# M7105B.net
KiCad netlist of a schematic drawn in EAGLE
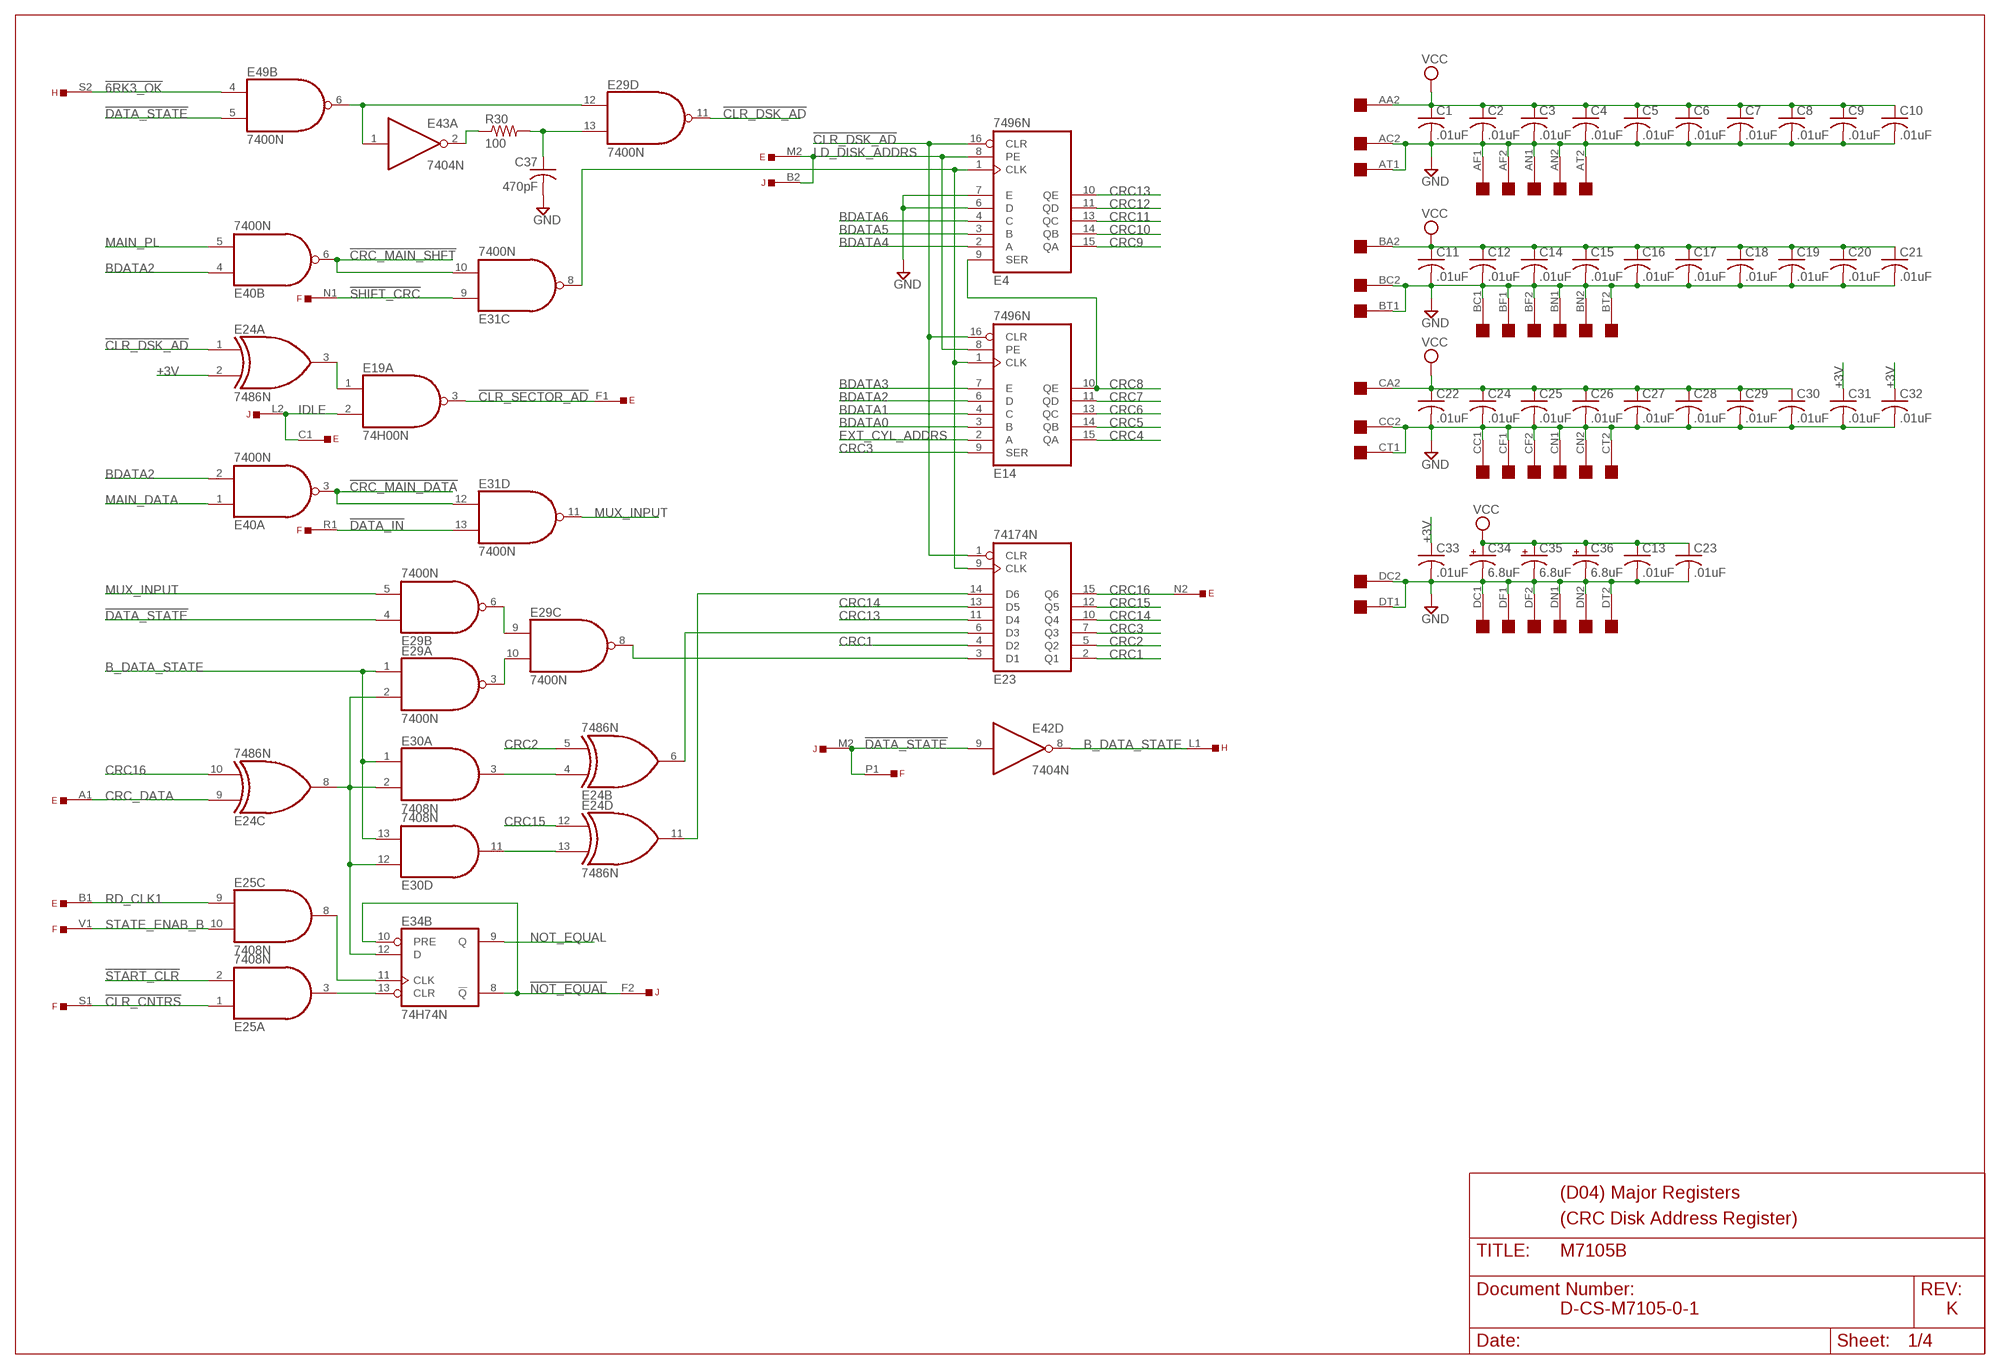
[diagram p0: schematic, sheet 1]
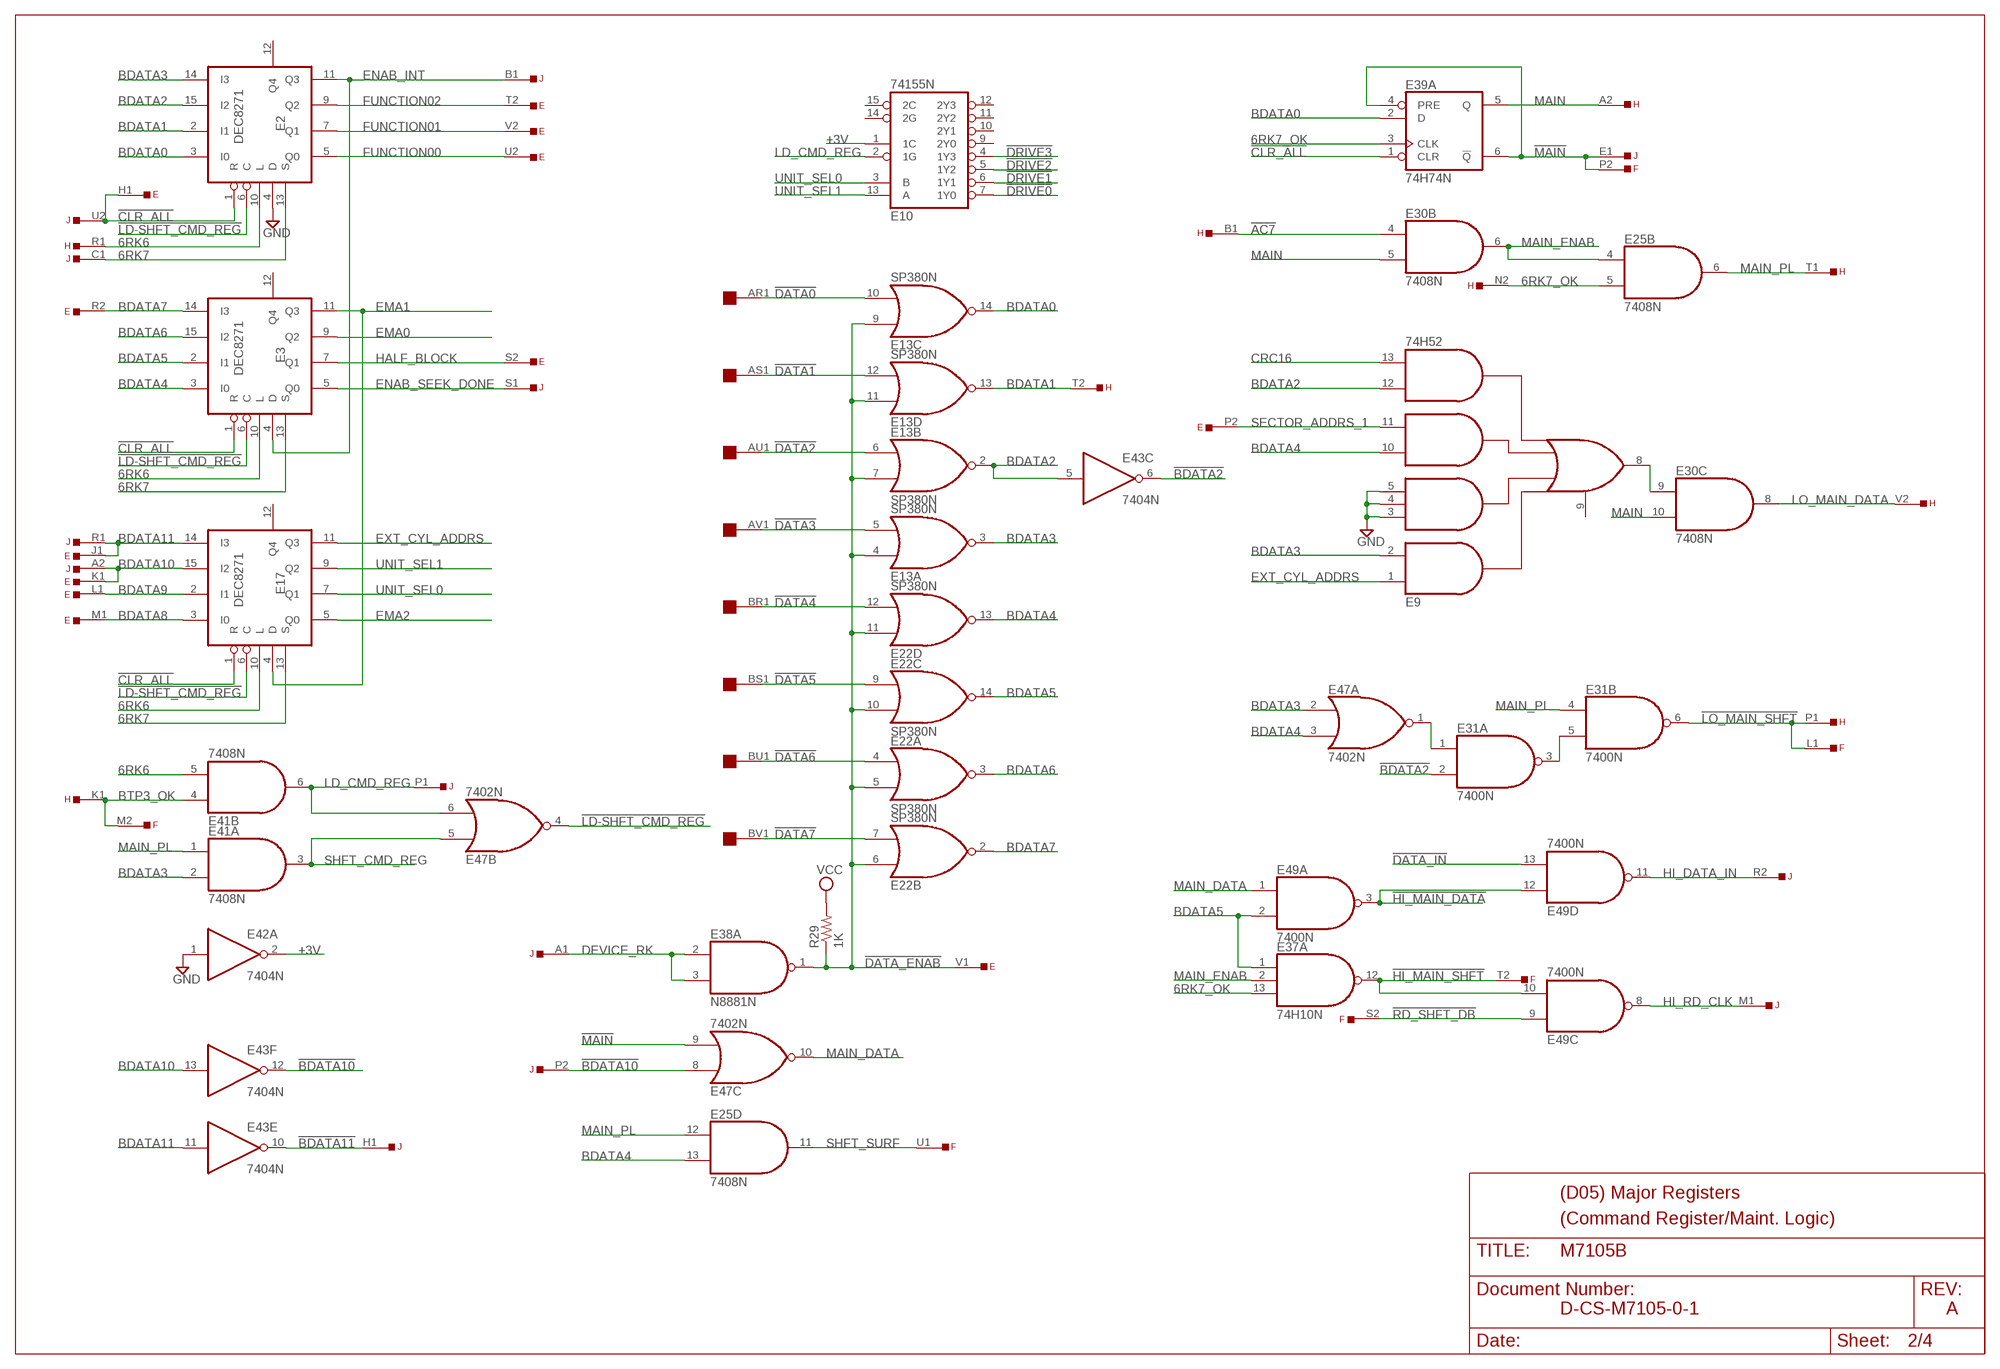
[diagram p1: schematic, sheet 2]
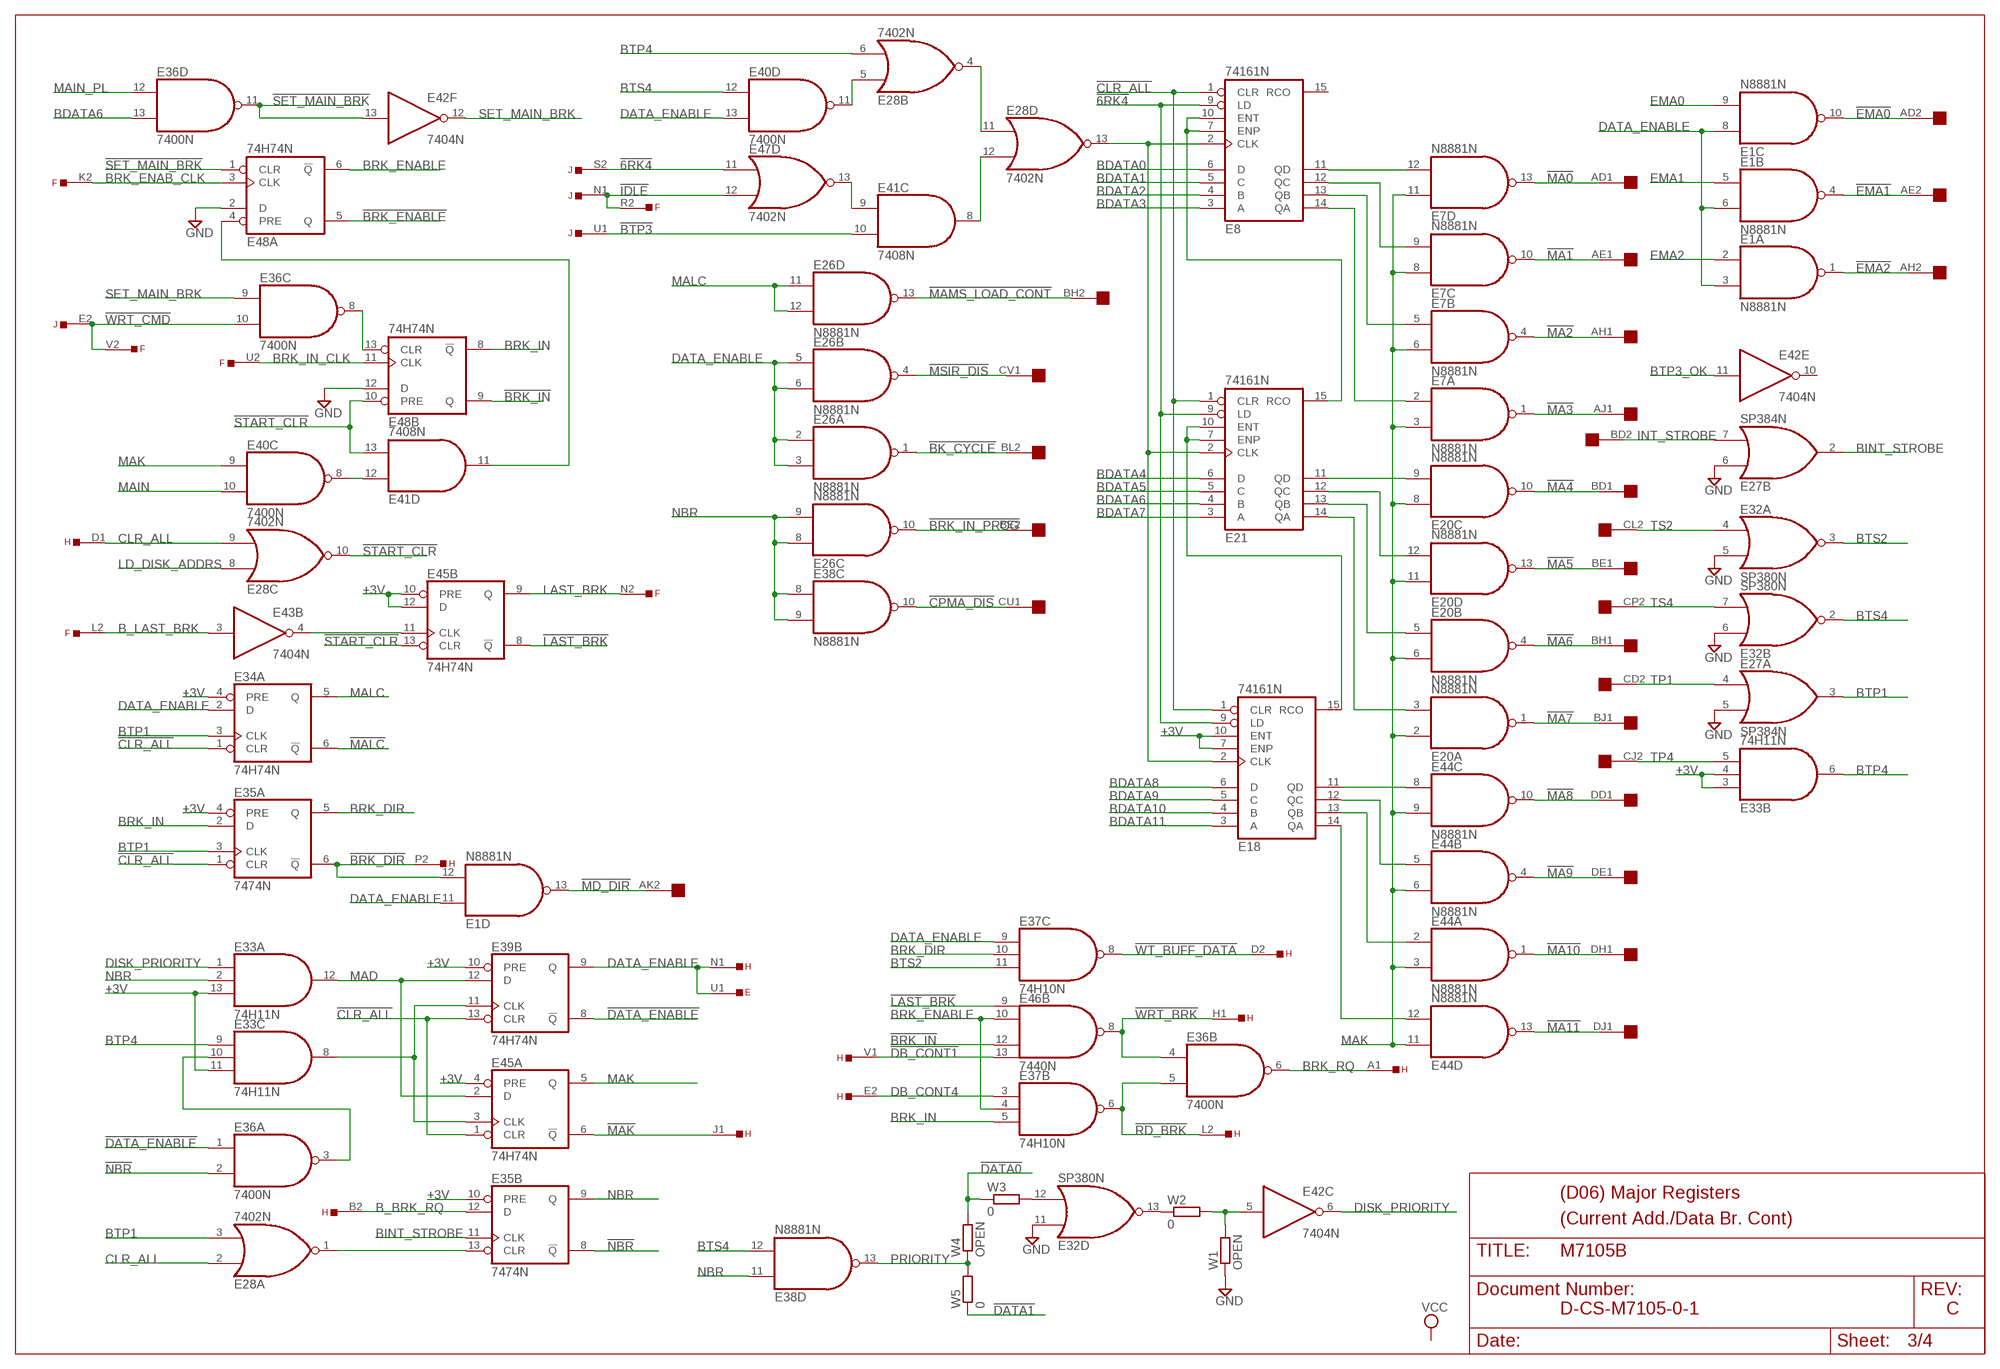
[diagram p2: schematic, sheet 3]
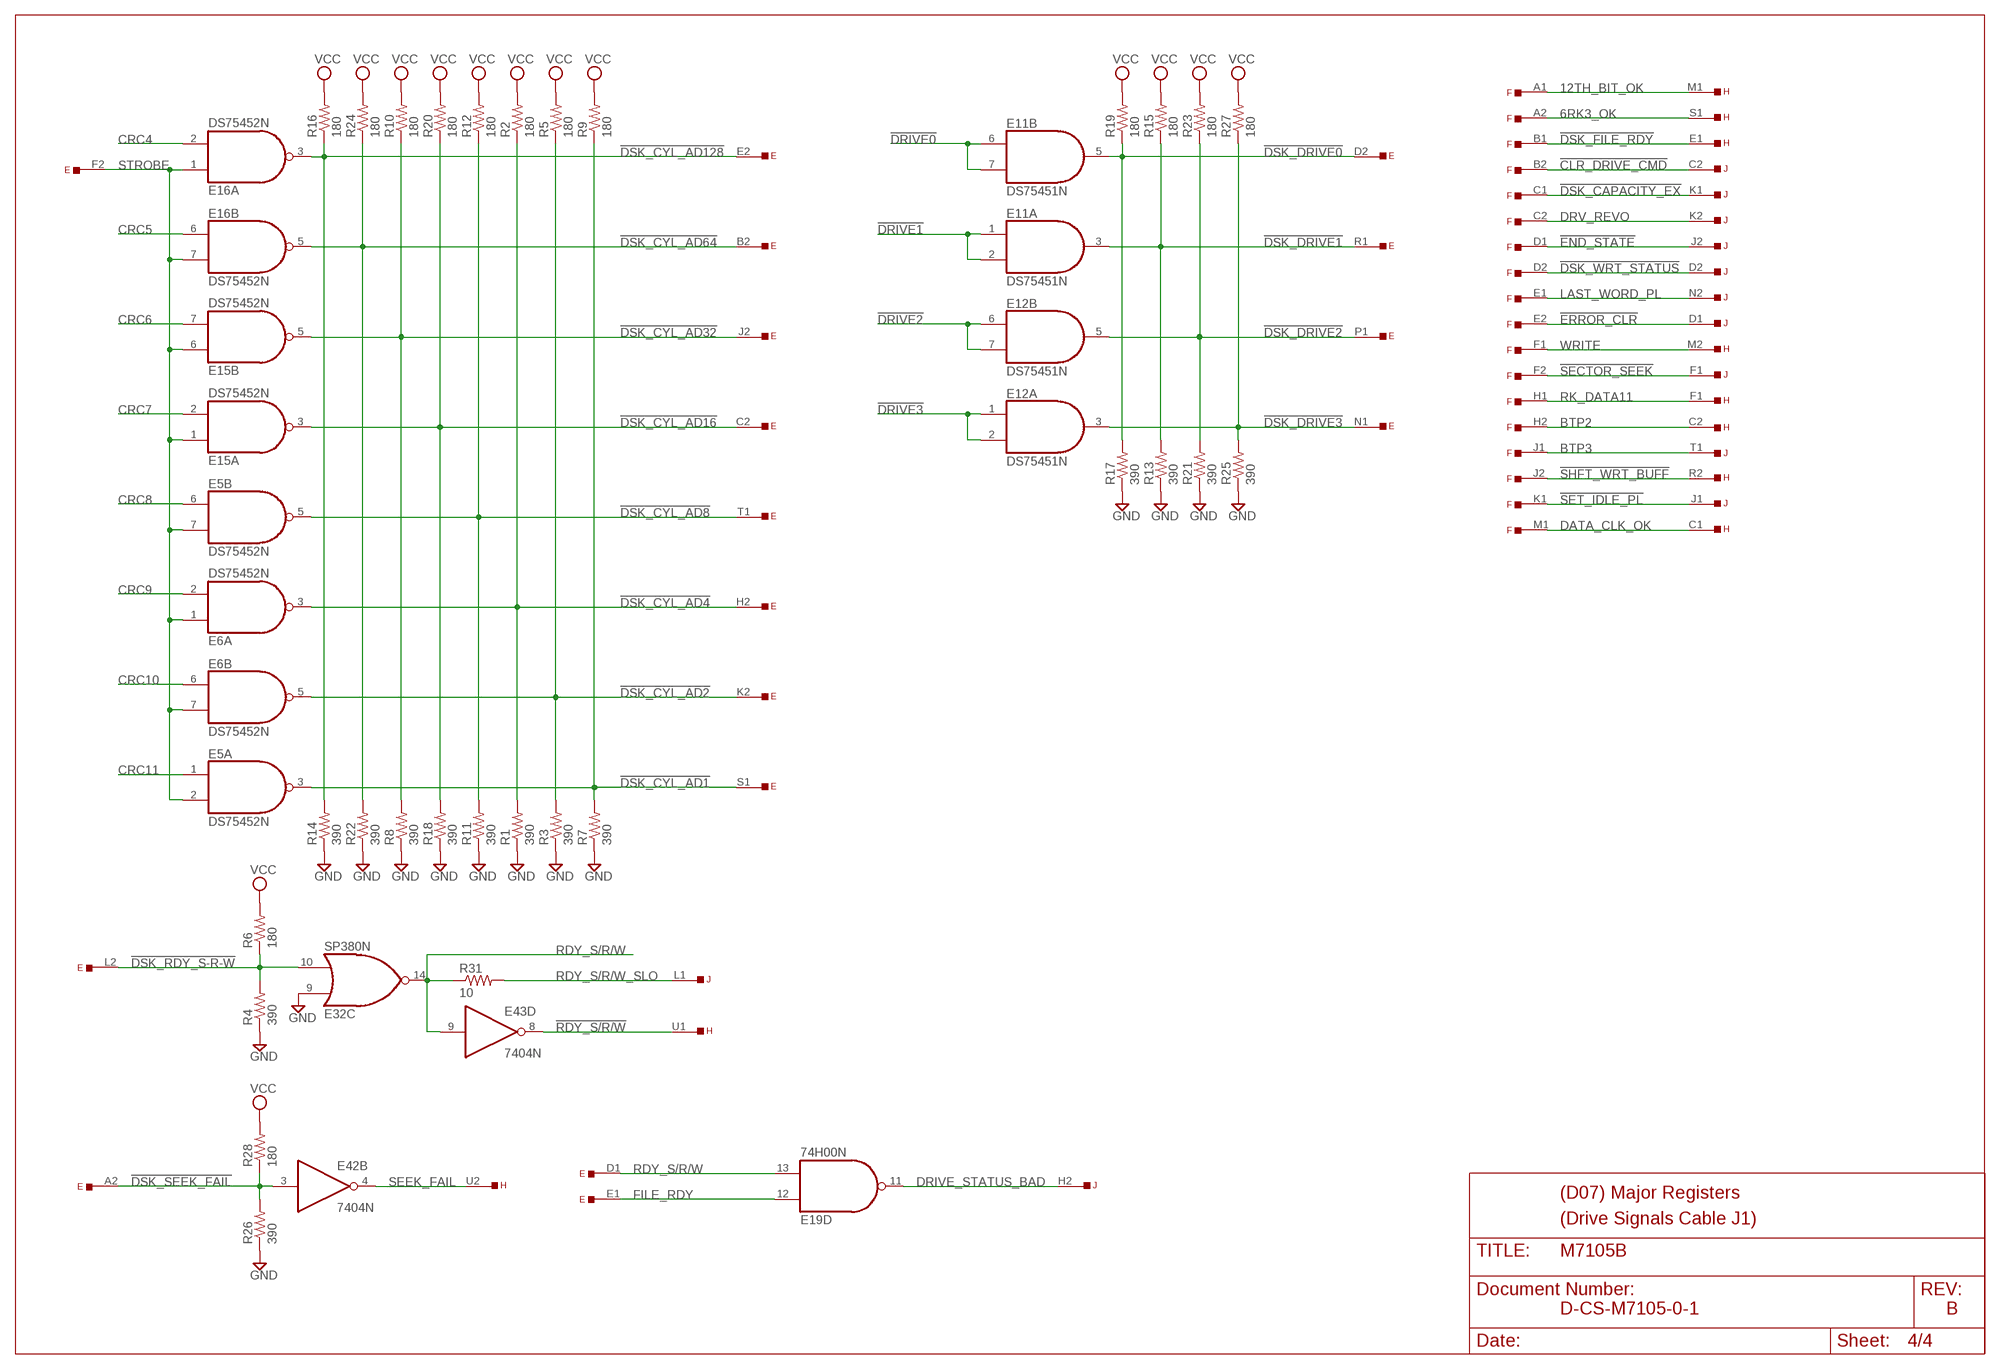
[diagram p3: schematic, sheet 4]

(export (version "E")
  (design (tool "Eeschema 10.0.6"))
  (components
    (comp (ref "E")
      (value "EDGE-TOP")
      (footprint "eagle-import:EDGE-CON2")
      (libsource (lib "eagle-import") (part "EDGE-TOP"))
    )
    (comp (ref "E2")
      (value "DEC8271")
      (footprint "eagle-import:DIL16")
      (libsource (lib "eagle-import") (part "DEC8271"))
    )
    (comp (ref "E3")
      (value "DEC8271")
      (footprint "eagle-import:DIL16")
      (libsource (lib "eagle-import") (part "DEC8271"))
    )
    (comp (ref "E9")
      (value "74H52")
      (footprint "eagle-import:DIL14")
      (libsource (lib "eagle-import") (part "7452H"))
    )
    (comp (ref "E10")
      (value "74155N")
      (footprint "eagle-import:DIL16")
      (libsource (lib "eagle-import") (part "74155N"))
    )
    (comp (ref "E13")
      (value "SP380N")
      (footprint "eagle-import:DIL14")
      (libsource (lib "eagle-import") (part "SP380N"))
    )
    (comp (ref "E17")
      (value "DEC8271")
      (footprint "eagle-import:DIL16")
      (libsource (lib "eagle-import") (part "DEC8271"))
    )
    (comp (ref "E22")
      (value "SP380N")
      (footprint "eagle-import:DIL14")
      (libsource (lib "eagle-import") (part "SP380N"))
    )
    (comp (ref "E25")
      (value "7408N")
      (footprint "eagle-import:DIL14")
      (libsource (lib "eagle-import") (part "7408NS"))
    )
    (comp (ref "E30")
      (value "7408N")
      (footprint "eagle-import:DIL14")
      (libsource (lib "eagle-import") (part "7408NS"))
    )
    (comp (ref "E31")
      (value "7400N")
      (footprint "eagle-import:DIL14")
      (libsource (lib "eagle-import") (part "7400N"))
    )
    (comp (ref "E37")
      (value "74H10N")
      (footprint "eagle-import:DIL14")
      (libsource (lib "eagle-import") (part "7410N"))
    )
    (comp (ref "E38")
      (value "N8881N")
      (footprint "eagle-import:DIL14")
      (libsource (lib "eagle-import") (part "N8881N"))
    )
    (comp (ref "E39")
      (value "74H74N")
      (footprint "eagle-import:DIL14")
      (libsource (lib "eagle-import") (part "7474NS"))
    )
    (comp (ref "E41")
      (value "7408N")
      (footprint "eagle-import:DIL14")
      (libsource (lib "eagle-import") (part "7408NS"))
    )
    (comp (ref "E42")
      (value "7404N")
      (footprint "eagle-import:DIL14")
      (libsource (lib "eagle-import") (part "7404N"))
    )
    (comp (ref "E43")
      (value "7404N")
      (footprint "eagle-import:DIL14")
      (libsource (lib "eagle-import") (part "7404N"))
    )
    (comp (ref "E47")
      (value "7402N")
      (footprint "eagle-import:DIL14")
      (libsource (lib "eagle-import") (part "7402N"))
    )
    (comp (ref "E49")
      (value "7400N")
      (footprint "eagle-import:DIL14")
      (libsource (lib "eagle-import") (part "7400N"))
    )
    (comp (ref "F")
      (value "EDGE-TOP")
      (footprint "eagle-import:EDGE-CON2")
      (libsource (lib "eagle-import") (part "EDGE-TOP"))
    )
    (comp (ref "H")
      (value "EDGE-TOP")
      (footprint "eagle-import:EDGE-CON2")
      (libsource (lib "eagle-import") (part "EDGE-TOP"))
    )
    (comp (ref "J")
      (value "EDGE-TOP")
      (footprint "eagle-import:EDGE-CON2")
      (libsource (lib "eagle-import") (part "EDGE-TOP"))
    )
    (comp (ref "OMNIBUS")
      (value "QUAD")
      (footprint "eagle-import:EDGE-CON8")
      (libsource (lib "eagle-import") (part "QUAD"))
    )
    (comp (ref "R29")
      (value "1K")
      (footprint "eagle-import:0207_10")
      (libsource (lib "eagle-import") (part "R-US_0207/10"))
    )
    (comp (ref "C1")
      (value ".01uF")
      (footprint "eagle-import:C063-025X075")
      (libsource (lib "eagle-import") (part "C-US"))
    )
    (comp (ref "C2")
      (value ".01uF")
      (footprint "eagle-import:C063-025X075")
      (libsource (lib "eagle-import") (part "C-US"))
    )
    (comp (ref "C3")
      (value ".01uF")
      (footprint "eagle-import:C063-025X075")
      (libsource (lib "eagle-import") (part "C-US"))
    )
    (comp (ref "C4")
      (value ".01uF")
      (footprint "eagle-import:C063-025X075")
      (libsource (lib "eagle-import") (part "C-US"))
    )
    (comp (ref "C5")
      (value ".01uF")
      (footprint "eagle-import:C063-025X075")
      (libsource (lib "eagle-import") (part "C-US"))
    )
    (comp (ref "C6")
      (value ".01uF")
      (footprint "eagle-import:C063-025X075")
      (libsource (lib "eagle-import") (part "C-US"))
    )
    (comp (ref "C7")
      (value ".01uF")
      (footprint "eagle-import:C063-025X075")
      (libsource (lib "eagle-import") (part "C-US"))
    )
    (comp (ref "C8")
      (value ".01uF")
      (footprint "eagle-import:C063-025X075")
      (libsource (lib "eagle-import") (part "C-US"))
    )
    (comp (ref "C9")
      (value ".01uF")
      (footprint "eagle-import:C063-025X075")
      (libsource (lib "eagle-import") (part "C-US"))
    )
    (comp (ref "C10")
      (value ".01uF")
      (footprint "eagle-import:C063-025X075")
      (libsource (lib "eagle-import") (part "C-US"))
    )
    (comp (ref "C11")
      (value ".01uF")
      (footprint "eagle-import:C063-025X075")
      (libsource (lib "eagle-import") (part "C-US"))
    )
    (comp (ref "C12")
      (value ".01uF")
      (footprint "eagle-import:C063-025X075")
      (libsource (lib "eagle-import") (part "C-US"))
    )
    (comp (ref "C13")
      (value ".01uF")
      (footprint "eagle-import:C063-025X075")
      (libsource (lib "eagle-import") (part "C-US"))
    )
    (comp (ref "C14")
      (value ".01uF")
      (footprint "eagle-import:C063-025X075")
      (libsource (lib "eagle-import") (part "C-US"))
    )
    (comp (ref "C15")
      (value ".01uF")
      (footprint "eagle-import:C063-025X075")
      (libsource (lib "eagle-import") (part "C-US"))
    )
    (comp (ref "C16")
      (value ".01uF")
      (footprint "eagle-import:C063-025X075")
      (libsource (lib "eagle-import") (part "C-US"))
    )
    (comp (ref "C17")
      (value ".01uF")
      (footprint "eagle-import:C063-025X075")
      (libsource (lib "eagle-import") (part "C-US"))
    )
    (comp (ref "C18")
      (value ".01uF")
      (footprint "eagle-import:C063-025X075")
      (libsource (lib "eagle-import") (part "C-US"))
    )
    (comp (ref "C19")
      (value ".01uF")
      (footprint "eagle-import:C063-025X075")
      (libsource (lib "eagle-import") (part "C-US"))
    )
    (comp (ref "C20")
      (value ".01uF")
      (footprint "eagle-import:C063-025X075")
      (libsource (lib "eagle-import") (part "C-US"))
    )
    (comp (ref "C21")
      (value ".01uF")
      (footprint "eagle-import:C063-025X075")
      (libsource (lib "eagle-import") (part "C-US"))
    )
    (comp (ref "C22")
      (value ".01uF")
      (footprint "eagle-import:C063-025X075")
      (libsource (lib "eagle-import") (part "C-US"))
    )
    (comp (ref "C23")
      (value ".01uF")
      (footprint "eagle-import:C063-025X075")
      (libsource (lib "eagle-import") (part "C-US"))
    )
    (comp (ref "C24")
      (value ".01uF")
      (footprint "eagle-import:C063-025X075")
      (libsource (lib "eagle-import") (part "C-US"))
    )
    (comp (ref "C25")
      (value ".01uF")
      (footprint "eagle-import:C063-025X075")
      (libsource (lib "eagle-import") (part "C-US"))
    )
    (comp (ref "C26")
      (value ".01uF")
      (footprint "eagle-import:C063-025X075")
      (libsource (lib "eagle-import") (part "C-US"))
    )
    (comp (ref "C27")
      (value ".01uF")
      (footprint "eagle-import:C063-025X075")
      (libsource (lib "eagle-import") (part "C-US"))
    )
    (comp (ref "C28")
      (value ".01uF")
      (footprint "eagle-import:C063-025X075")
      (libsource (lib "eagle-import") (part "C-US"))
    )
    (comp (ref "C29")
      (value ".01uF")
      (footprint "eagle-import:C063-025X075")
      (libsource (lib "eagle-import") (part "C-US"))
    )
    (comp (ref "C30")
      (value ".01uF")
      (footprint "eagle-import:C063-025X075")
      (libsource (lib "eagle-import") (part "C-US"))
    )
    (comp (ref "C31")
      (value ".01uF")
      (footprint "eagle-import:C063-025X075")
      (libsource (lib "eagle-import") (part "C-US"))
    )
    (comp (ref "C32")
      (value ".01uF")
      (footprint "eagle-import:C063-025X075")
      (libsource (lib "eagle-import") (part "C-US"))
    )
    (comp (ref "C33")
      (value ".01uF")
      (footprint "eagle-import:C063-025X075")
      (libsource (lib "eagle-import") (part "C-US"))
    )
    (comp (ref "C34")
      (value "6.8uF")
      (footprint "eagle-import:E12-8")
      (libsource (lib "eagle-import") (part "CPOL-USE20-8AXIAL"))
    )
    (comp (ref "C35")
      (value "6.8uF")
      (footprint "eagle-import:E12-8")
      (libsource (lib "eagle-import") (part "CPOL-USE20-8AXIAL"))
    )
    (comp (ref "C36")
      (value "6.8uF")
      (footprint "eagle-import:E12-8")
      (libsource (lib "eagle-import") (part "CPOL-USE20-8AXIAL"))
    )
    (comp (ref "C37")
      (value "470pF")
      (footprint "eagle-import:C063-025X075")
      (libsource (lib "eagle-import") (part "C-US"))
    )
    (comp (ref "E4")
      (value "7496N")
      (footprint "eagle-import:DIL16")
      (libsource (lib "eagle-import") (part "7496NLS"))
    )
    (comp (ref "E14")
      (value "7496N")
      (footprint "eagle-import:DIL16")
      (libsource (lib "eagle-import") (part "7496NLS"))
    )
    (comp (ref "E19")
      (value "74H00N")
      (footprint "eagle-import:DIL14")
      (libsource (lib "eagle-import") (part "7400NS"))
    )
    (comp (ref "E23")
      (value "74174N")
      (footprint "eagle-import:DIL16")
      (libsource (lib "eagle-import") (part "74174N"))
    )
    (comp (ref "E24")
      (value "7486N")
      (footprint "eagle-import:DIL14")
      (libsource (lib "eagle-import") (part "7486N"))
    )
    (comp (ref "E29")
      (value "7400N")
      (footprint "eagle-import:DIL14")
      (libsource (lib "eagle-import") (part "7400N"))
    )
    (comp (ref "E34")
      (value "74H74N")
      (footprint "eagle-import:DIL14")
      (libsource (lib "eagle-import") (part "7474NS"))
    )
    (comp (ref "E40")
      (value "7400N")
      (footprint "eagle-import:DIL14")
      (libsource (lib "eagle-import") (part "7400N"))
    )
    (comp (ref "R30")
      (value "100")
      (footprint "eagle-import:0207_10")
      (libsource (lib "eagle-import") (part "R-US_0207/10"))
    )
    (comp (ref "E1")
      (value "N8881N")
      (footprint "eagle-import:DIL14")
      (libsource (lib "eagle-import") (part "N8881N"))
    )
    (comp (ref "E7")
      (value "N8881N")
      (footprint "eagle-import:DIL14")
      (libsource (lib "eagle-import") (part "N8881N"))
    )
    (comp (ref "E8")
      (value "74161N")
      (footprint "eagle-import:DIL16")
      (libsource (lib "eagle-import") (part "74161N"))
    )
    (comp (ref "E18")
      (value "74161N")
      (footprint "eagle-import:DIL16")
      (libsource (lib "eagle-import") (part "74161N"))
    )
    (comp (ref "E20")
      (value "N8881N")
      (footprint "eagle-import:DIL14")
      (libsource (lib "eagle-import") (part "N8881N"))
    )
    (comp (ref "E21")
      (value "74161N")
      (footprint "eagle-import:DIL16")
      (libsource (lib "eagle-import") (part "74161N"))
    )
    (comp (ref "E26")
      (value "N8881N")
      (footprint "eagle-import:DIL14")
      (libsource (lib "eagle-import") (part "N8881N"))
    )
    (comp (ref "E27")
      (value "SP384N")
      (footprint "eagle-import:DIL14")
      (libsource (lib "eagle-import") (part "SP384N"))
    )
    (comp (ref "E28")
      (value "7402N")
      (footprint "eagle-import:DIL14")
      (libsource (lib "eagle-import") (part "7402N"))
    )
    (comp (ref "E32")
      (value "SP380N")
      (footprint "eagle-import:DIL14")
      (libsource (lib "eagle-import") (part "SP380N"))
    )
    (comp (ref "E33")
      (value "74H11N")
      (footprint "eagle-import:DIL14")
      (libsource (lib "eagle-import") (part "7411NS"))
    )
    (comp (ref "E35")
      (value "7474N")
      (footprint "eagle-import:DIL14")
      (libsource (lib "eagle-import") (part "7474NS"))
    )
    (comp (ref "E36")
      (value "7400N")
      (footprint "eagle-import:DIL14")
      (libsource (lib "eagle-import") (part "7400N"))
    )
    (comp (ref "E44")
      (value "N8881N")
      (footprint "eagle-import:DIL14")
      (libsource (lib "eagle-import") (part "N8881N"))
    )
    (comp (ref "E45")
      (value "74H74N")
      (footprint "eagle-import:DIL14")
      (libsource (lib "eagle-import") (part "7474NS"))
    )
    (comp (ref "E46")
      (value "7440N")
      (footprint "eagle-import:DIL14")
      (libsource (lib "eagle-import") (part "7440N"))
    )
    (comp (ref "E48")
      (value "74H74N")
      (footprint "eagle-import:DIL14")
      (libsource (lib "eagle-import") (part "7474NS"))
    )
    (comp (ref "W1")
      (value "OPEN")
      (footprint "eagle-import:0204_7")
      (libsource (lib "eagle-import") (part "R-EU_0204/7"))
    )
    (comp (ref "W2")
      (value "0")
      (footprint "eagle-import:0204_7")
      (libsource (lib "eagle-import") (part "R-EU_0204/7"))
    )
    (comp (ref "W3")
      (value "0")
      (footprint "eagle-import:0204_5")
      (libsource (lib "eagle-import") (part "R-EU_0204/5"))
    )
    (comp (ref "W4")
      (value "OPEN")
      (footprint "eagle-import:0204_5")
      (libsource (lib "eagle-import") (part "R-EU_0204/5"))
    )
    (comp (ref "W5")
      (value "0")
      (footprint "eagle-import:0204_5")
      (libsource (lib "eagle-import") (part "R-EU_0204/5"))
    )
    (comp (ref "E5")
      (value "DS75452N")
      (footprint "eagle-import:DIL08")
      (libsource (lib "eagle-import") (part "DS75452N"))
    )
    (comp (ref "E6")
      (value "DS75452N")
      (footprint "eagle-import:DIL08")
      (libsource (lib "eagle-import") (part "DS75452N"))
    )
    (comp (ref "E11")
      (value "DS75451N")
      (footprint "eagle-import:DIL08")
      (libsource (lib "eagle-import") (part "DS75451N"))
    )
    (comp (ref "E12")
      (value "DS75451N")
      (footprint "eagle-import:DIL08")
      (libsource (lib "eagle-import") (part "DS75451N"))
    )
    (comp (ref "E15")
      (value "DS75452N")
      (footprint "eagle-import:DIL08")
      (libsource (lib "eagle-import") (part "DS75452N"))
    )
    (comp (ref "E16")
      (value "DS75452N")
      (footprint "eagle-import:DIL08")
      (libsource (lib "eagle-import") (part "DS75452N"))
    )
    (comp (ref "R1")
      (value "390")
      (footprint "eagle-import:0207_10")
      (libsource (lib "eagle-import") (part "R-US_0207/10"))
    )
    (comp (ref "R2")
      (value "180")
      (footprint "eagle-import:0207_10")
      (libsource (lib "eagle-import") (part "R-US_0207/10"))
    )
    (comp (ref "R3")
      (value "390")
      (footprint "eagle-import:0207_10")
      (libsource (lib "eagle-import") (part "R-US_0207/10"))
    )
    (comp (ref "R4")
      (value "390")
      (footprint "eagle-import:0207_10")
      (libsource (lib "eagle-import") (part "R-US_0207/10"))
    )
    (comp (ref "R5")
      (value "180")
      (footprint "eagle-import:0207_10")
      (libsource (lib "eagle-import") (part "R-US_0207/10"))
    )
    (comp (ref "R6")
      (value "180")
      (footprint "eagle-import:0207_10")
      (libsource (lib "eagle-import") (part "R-US_0207/10"))
    )
    (comp (ref "R7")
      (value "390")
      (footprint "eagle-import:0207_10")
      (libsource (lib "eagle-import") (part "R-US_0207/10"))
    )
    (comp (ref "R8")
      (value "390")
      (footprint "eagle-import:0207_10")
      (libsource (lib "eagle-import") (part "R-US_0207/10"))
    )
    (comp (ref "R9")
      (value "180")
      (footprint "eagle-import:0207_10")
      (libsource (lib "eagle-import") (part "R-US_0207/10"))
    )
    (comp (ref "R10")
      (value "180")
      (footprint "eagle-import:0207_10")
      (libsource (lib "eagle-import") (part "R-US_0207/10"))
    )
    (comp (ref "R11")
      (value "390")
      (footprint "eagle-import:0207_10")
      (libsource (lib "eagle-import") (part "R-US_0207/10"))
    )
    (comp (ref "R12")
      (value "180")
      (footprint "eagle-import:0207_10")
      (libsource (lib "eagle-import") (part "R-US_0207/10"))
    )
    (comp (ref "R13")
      (value "390")
      (footprint "eagle-import:0207_10")
      (libsource (lib "eagle-import") (part "R-US_0207/10"))
    )
    (comp (ref "R14")
      (value "390")
      (footprint "eagle-import:0207_10")
      (libsource (lib "eagle-import") (part "R-US_0207/10"))
    )
    (comp (ref "R15")
      (value "180")
      (footprint "eagle-import:0207_10")
      (libsource (lib "eagle-import") (part "R-US_0207/10"))
    )
    (comp (ref "R16")
      (value "180")
      (footprint "eagle-import:0207_10")
      (libsource (lib "eagle-import") (part "R-US_0207/10"))
    )
    (comp (ref "R17")
      (value "390")
      (footprint "eagle-import:0207_10")
      (libsource (lib "eagle-import") (part "R-US_0207/10"))
    )
    (comp (ref "R18")
      (value "390")
      (footprint "eagle-import:0207_10")
      (libsource (lib "eagle-import") (part "R-US_0207/10"))
    )
    (comp (ref "R19")
      (value "180")
      (footprint "eagle-import:0207_10")
      (libsource (lib "eagle-import") (part "R-US_0207/10"))
    )
    (comp (ref "R20")
      (value "180")
      (footprint "eagle-import:0207_10")
      (libsource (lib "eagle-import") (part "R-US_0207/10"))
    )
    (comp (ref "R21")
      (value "390")
      (footprint "eagle-import:0207_10")
      (libsource (lib "eagle-import") (part "R-US_0207/10"))
    )
    (comp (ref "R22")
      (value "390")
      (footprint "eagle-import:0207_10")
      (libsource (lib "eagle-import") (part "R-US_0207/10"))
    )
    (comp (ref "R23")
      (value "180")
      (footprint "eagle-import:0207_10")
      (libsource (lib "eagle-import") (part "R-US_0207/10"))
    )
    (comp (ref "R24")
      (value "180")
      (footprint "eagle-import:0207_10")
      (libsource (lib "eagle-import") (part "R-US_0207/10"))
    )
    (comp (ref "R25")
      (value "390")
      (footprint "eagle-import:0207_10")
      (libsource (lib "eagle-import") (part "R-US_0207/10"))
    )
    (comp (ref "R26")
      (value "390")
      (footprint "eagle-import:0207_10")
      (libsource (lib "eagle-import") (part "R-US_0207/10"))
    )
    (comp (ref "R27")
      (value "180")
      (footprint "eagle-import:0207_10")
      (libsource (lib "eagle-import") (part "R-US_0207/10"))
    )
    (comp (ref "R28")
      (value "180")
      (footprint "eagle-import:0207_10")
      (libsource (lib "eagle-import") (part "R-US_0207/10"))
    )
    (comp (ref "R31")
      (value "10")
      (footprint "eagle-import:0207_10")
      (libsource (lib "eagle-import") (part "R-US_0207/10"))
    )
  )
  (nets
    (net (code "1") (name "+3V") (class "Default")
      (node (ref "C31") (pin "1") (pinfunction "1_1") (pintype "passive"))
      (node (ref "C32") (pin "1") (pinfunction "1_1") (pintype "passive"))
      (node (ref "C33") (pin "1") (pinfunction "1_1") (pintype "passive"))
      (node (ref "E10") (pin "1") (pinfunction "1C_1") (pintype "input"))
      (node (ref "E18") (pin "10") (pinfunction "ENT_10") (pintype "input"))
      (node (ref "E18") (pin "7") (pinfunction "ENP_7") (pintype "input"))
      (node (ref "E24") (pin "2") (pinfunction "I1_2") (pintype "input"))
      (node (ref "E33") (pin "11") (pinfunction "I2_11") (pintype "input"))
      (node (ref "E33") (pin "13") (pinfunction "I2_13") (pintype "input"))
      (node (ref "E33") (pin "3") (pinfunction "I0_3") (pintype "input"))
      (node (ref "E33") (pin "4") (pinfunction "I1_4") (pintype "input"))
      (node (ref "E34") (pin "4") (pinfunction "PRE_4") (pintype "input"))
      (node (ref "E35") (pin "10") (pinfunction "PRE_10") (pintype "input"))
      (node (ref "E35") (pin "4") (pinfunction "PRE_4") (pintype "input"))
      (node (ref "E39") (pin "10") (pinfunction "PRE_10") (pintype "input"))
      (node (ref "E42") (pin "2") (pinfunction "O_2") (pintype "output"))
      (node (ref "E45") (pin "10") (pinfunction "PRE_10") (pintype "input"))
      (node (ref "E45") (pin "12") (pinfunction "D_12") (pintype "input"))
      (node (ref "E45") (pin "4") (pinfunction "PRE_4") (pintype "input"))
    )
    (net (code "2") (name "6RK3_OK") (class "Default")
      (node (ref "F") (pin "A2") (pinfunction "P_A2") (pintype "passive"))
      (node (ref "H") (pin "S1") (pinfunction "P_S1") (pintype "passive"))
    )
    (net (code "3") (name "6RK6") (class "Default")
      (node (ref "E17") (pin "10") (pinfunction "L_10") (pintype "input"))
      (node (ref "E2") (pin "10") (pinfunction "L_10") (pintype "input"))
      (node (ref "E3") (pin "10") (pinfunction "L_10") (pintype "input"))
      (node (ref "E41") (pin "5") (pinfunction "I1_5") (pintype "input"))
      (node (ref "H") (pin "R1") (pinfunction "P_R1") (pintype "passive"))
    )
    (net (code "4") (name "6RK7") (class "Default")
      (node (ref "E17") (pin "13") (pinfunction "S_13") (pintype "input"))
      (node (ref "E2") (pin "13") (pinfunction "S_13") (pintype "input"))
      (node (ref "E3") (pin "13") (pinfunction "S_13") (pintype "input"))
      (node (ref "J") (pin "C1") (pinfunction "P_C1") (pintype "passive"))
    )
    (net (code "5") (name "6RK7_OK") (class "Default")
      (node (ref "E25") (pin "5") (pinfunction "I1_5") (pintype "input"))
      (node (ref "E37") (pin "13") (pinfunction "I2_13") (pintype "input"))
      (node (ref "E39") (pin "3") (pinfunction "CLK_3") (pintype "input"))
      (node (ref "H") (pin "N2") (pinfunction "P_N2") (pintype "passive"))
    )
    (net (code "6") (name "12TH_BIT_OK") (class "Default")
      (node (ref "F") (pin "A1") (pinfunction "P_A1") (pintype "passive"))
      (node (ref "H") (pin "M1") (pinfunction "P_M1") (pintype "passive"))
    )
    (net (code "7") (name "BDATA0") (class "Default")
      (node (ref "E13") (pin "14") (pinfunction "O_14") (pintype "output"))
      (node (ref "E14") (pin "3") (pinfunction "B_3") (pintype "input"))
      (node (ref "E2") (pin "3") (pinfunction "I0_3") (pintype "input"))
      (node (ref "E39") (pin "2") (pinfunction "D_2") (pintype "input"))
      (node (ref "E8") (pin "6") (pinfunction "D_6") (pintype "input"))
    )
    (net (code "8") (name "BDATA1") (class "Default")
      (node (ref "E13") (pin "13") (pinfunction "O_13") (pintype "output"))
      (node (ref "E14") (pin "4") (pinfunction "C_4") (pintype "input"))
      (node (ref "E2") (pin "2") (pinfunction "I1_2") (pintype "input"))
      (node (ref "E8") (pin "5") (pinfunction "C_5") (pintype "input"))
      (node (ref "H") (pin "T2") (pinfunction "P_T2") (pintype "passive"))
    )
    (net (code "9") (name "BDATA2") (class "Default")
      (node (ref "E13") (pin "2") (pinfunction "O_2") (pintype "output"))
      (node (ref "E14") (pin "6") (pinfunction "D_6") (pintype "input"))
      (node (ref "E2") (pin "15") (pinfunction "I2_15") (pintype "input"))
      (node (ref "E40") (pin "2") (pinfunction "I1_2") (pintype "input"))
      (node (ref "E40") (pin "4") (pinfunction "I0_4") (pintype "input"))
      (node (ref "E43") (pin "5") (pinfunction "I_5") (pintype "input"))
      (node (ref "E8") (pin "4") (pinfunction "B_4") (pintype "input"))
      (node (ref "E9") (pin "12") (pinfunction "I12_12") (pintype "input"))
    )
    (net (code "10") (name "BDATA3") (class "Default")
      (node (ref "E13") (pin "3") (pinfunction "O_3") (pintype "output"))
      (node (ref "E14") (pin "7") (pinfunction "E_7") (pintype "input"))
      (node (ref "E2") (pin "14") (pinfunction "I3_14") (pintype "input"))
      (node (ref "E41") (pin "2") (pinfunction "I1_2") (pintype "input"))
      (node (ref "E47") (pin "2") (pinfunction "I0_2") (pintype "input"))
      (node (ref "E8") (pin "3") (pinfunction "A_3") (pintype "input"))
      (node (ref "E9") (pin "2") (pinfunction "I2_2") (pintype "input"))
    )
    (net (code "11") (name "BDATA4") (class "Default")
      (node (ref "E21") (pin "6") (pinfunction "D_6") (pintype "input"))
      (node (ref "E22") (pin "13") (pinfunction "O_13") (pintype "output"))
      (node (ref "E25") (pin "13") (pinfunction "I1_13") (pintype "input"))
      (node (ref "E3") (pin "3") (pinfunction "I0_3") (pintype "input"))
      (node (ref "E4") (pin "2") (pinfunction "A_2") (pintype "input"))
      (node (ref "E47") (pin "3") (pinfunction "I1_3") (pintype "input"))
      (node (ref "E9") (pin "10") (pinfunction "I10_10") (pintype "input"))
    )
    (net (code "12") (name "BDATA5") (class "Default")
      (node (ref "E21") (pin "5") (pinfunction "C_5") (pintype "input"))
      (node (ref "E22") (pin "14") (pinfunction "O_14") (pintype "output"))
      (node (ref "E3") (pin "2") (pinfunction "I1_2") (pintype "input"))
      (node (ref "E37") (pin "1") (pinfunction "I0_1") (pintype "input"))
      (node (ref "E4") (pin "3") (pinfunction "B_3") (pintype "input"))
      (node (ref "E49") (pin "2") (pinfunction "I1_2") (pintype "input"))
    )
    (net (code "13") (name "BDATA6") (class "Default")
      (node (ref "E21") (pin "4") (pinfunction "B_4") (pintype "input"))
      (node (ref "E22") (pin "3") (pinfunction "O_3") (pintype "output"))
      (node (ref "E3") (pin "15") (pinfunction "I2_15") (pintype "input"))
      (node (ref "E36") (pin "13") (pinfunction "I1_13") (pintype "input"))
      (node (ref "E4") (pin "4") (pinfunction "C_4") (pintype "input"))
    )
    (net (code "14") (name "BDATA7") (class "Default")
      (node (ref "E") (pin "R2") (pinfunction "P_R2") (pintype "passive"))
      (node (ref "E21") (pin "3") (pinfunction "A_3") (pintype "input"))
      (node (ref "E22") (pin "2") (pinfunction "O_2") (pintype "output"))
      (node (ref "E3") (pin "14") (pinfunction "I3_14") (pintype "input"))
    )
    (net (code "15") (name "BDATA8") (class "Default")
      (node (ref "E") (pin "M1") (pinfunction "P_M1") (pintype "passive"))
      (node (ref "E17") (pin "3") (pinfunction "I0_3") (pintype "input"))
      (node (ref "E18") (pin "6") (pinfunction "D_6") (pintype "input"))
    )
    (net (code "16") (name "BDATA9") (class "Default")
      (node (ref "E") (pin "L1") (pinfunction "P_L1") (pintype "passive"))
      (node (ref "E17") (pin "2") (pinfunction "I1_2") (pintype "input"))
      (node (ref "E18") (pin "5") (pinfunction "C_5") (pintype "input"))
    )
    (net (code "17") (name "BDATA10") (class "Default")
      (node (ref "E") (pin "K1") (pinfunction "P_K1") (pintype "passive"))
      (node (ref "E17") (pin "15") (pinfunction "I2_15") (pintype "input"))
      (node (ref "E18") (pin "4") (pinfunction "B_4") (pintype "input"))
      (node (ref "E43") (pin "13") (pinfunction "I_13") (pintype "input"))
      (node (ref "J") (pin "A2") (pinfunction "P_A2") (pintype "passive"))
    )
    (net (code "18") (name "BDATA11") (class "Default")
      (node (ref "E") (pin "J1") (pinfunction "P_J1") (pintype "passive"))
      (node (ref "E17") (pin "14") (pinfunction "I3_14") (pintype "input"))
      (node (ref "E18") (pin "3") (pinfunction "A_3") (pintype "input"))
      (node (ref "E43") (pin "11") (pinfunction "I_11") (pintype "input"))
      (node (ref "J") (pin "R1") (pinfunction "P_R1") (pintype "passive"))
    )
    (net (code "19") (name "BINT_STROBE") (class "Default")
      (node (ref "E27") (pin "2") (pinfunction "O_2") (pintype "output"))
      (node (ref "E35") (pin "11") (pinfunction "CLK_11") (pintype "input"))
    )
    (net (code "20") (name "BRK_DIR") (class "Default")
      (node (ref "E35") (pin "5") (pinfunction "Q_5") (pintype "output"))
      (node (ref "E37") (pin "10") (pinfunction "I1_10") (pintype "input"))
    )
    (net (code "21") (name "BRK_ENABLE") (class "Default")
      (node (ref "E37") (pin "4") (pinfunction "I1_4") (pintype "input"))
      (node (ref "E46") (pin "10") (pinfunction "I1_10") (pintype "input"))
      (node (ref "E48") (pin "6") (pinfunction "~{Q}_6") (pintype "output"))
    )
    (net (code "22") (name "BRK_ENAB_CLK") (class "Default")
      (node (ref "E48") (pin "3") (pinfunction "CLK_3") (pintype "input"))
      (node (ref "F") (pin "K2") (pinfunction "P_K2") (pintype "passive"))
    )
    (net (code "23") (name "BRK_IN") (class "Default")
      (node (ref "E35") (pin "2") (pinfunction "D_2") (pintype "input"))
      (node (ref "E37") (pin "5") (pinfunction "I2_5") (pintype "input"))
      (node (ref "E48") (pin "8") (pinfunction "~{Q}_8") (pintype "output"))
    )
    (net (code "24") (name "BRK_IN_CLK") (class "Default")
      (node (ref "E48") (pin "11") (pinfunction "CLK_11") (pintype "input"))
      (node (ref "F") (pin "U2") (pinfunction "P_U2") (pintype "passive"))
    )
    (net (code "25") (name "BRK_RQ") (class "Default")
      (node (ref "E36") (pin "6") (pinfunction "O_6") (pintype "output"))
      (node (ref "H") (pin "A1") (pinfunction "P_A1") (pintype "passive"))
    )
    (net (code "26") (name "BTP1") (class "Default")
      (node (ref "E27") (pin "3") (pinfunction "O_3") (pintype "output"))
      (node (ref "E28") (pin "3") (pinfunction "I1_3") (pintype "input"))
      (node (ref "E34") (pin "3") (pinfunction "CLK_3") (pintype "input"))
      (node (ref "E35") (pin "3") (pinfunction "CLK_3") (pintype "input"))
    )
    (net (code "27") (name "BTP2") (class "Default")
      (node (ref "F") (pin "H2") (pinfunction "P_H2") (pintype "passive"))
      (node (ref "H") (pin "C2") (pinfunction "P_C2") (pintype "passive"))
    )
    (net (code "28") (name "BTP3") (class "Default")
      (node (ref "F") (pin "J1") (pinfunction "P_J1") (pintype "passive"))
      (node (ref "J") (pin "T1") (pinfunction "P_T1") (pintype "passive"))
    )
    (net (code "29") (name "BTP3_OK") (class "Default")
      (node (ref "E41") (pin "4") (pinfunction "I0_4") (pintype "input"))
      (node (ref "E42") (pin "11") (pinfunction "I_11") (pintype "input"))
      (node (ref "F") (pin "M2") (pinfunction "P_M2") (pintype "passive"))
      (node (ref "H") (pin "K1") (pinfunction "P_K1") (pintype "passive"))
    )
    (net (code "30") (name "BTP4") (class "Default")
      (node (ref "E28") (pin "6") (pinfunction "I1_6") (pintype "input"))
      (node (ref "E33") (pin "6") (pinfunction "O_6") (pintype "output"))
      (node (ref "E33") (pin "9") (pinfunction "I0_9") (pintype "input"))
    )
    (net (code "31") (name "BTS2") (class "Default")
      (node (ref "E32") (pin "3") (pinfunction "O_3") (pintype "output"))
      (node (ref "E37") (pin "11") (pinfunction "I2_11") (pintype "input"))
    )
    (net (code "32") (name "BTS4") (class "Default")
      (node (ref "E32") (pin "2") (pinfunction "O_2") (pintype "output"))
      (node (ref "E38") (pin "12") (pinfunction "I1_12") (pintype "input"))
      (node (ref "E40") (pin "12") (pinfunction "I0_12") (pintype "input"))
    )
    (net (code "33") (name "B_BRK_RQ") (class "Default")
      (node (ref "E35") (pin "12") (pinfunction "D_12") (pintype "input"))
      (node (ref "H") (pin "B2") (pinfunction "P_B2") (pintype "passive"))
    )
    (net (code "34") (name "B_DATA_STATE") (class "Default")
      (node (ref "E29") (pin "1") (pinfunction "I0_1") (pintype "input"))
      (node (ref "E30") (pin "1") (pinfunction "I0_1") (pintype "input"))
      (node (ref "E30") (pin "13") (pinfunction "I1_13") (pintype "input"))
      (node (ref "E42") (pin "8") (pinfunction "O_8") (pintype "output"))
      (node (ref "H") (pin "L1") (pinfunction "P_L1") (pintype "passive"))
    )
    (net (code "35") (name "B_LAST_BRK") (class "Default")
      (node (ref "E43") (pin "3") (pinfunction "I_3") (pintype "input"))
      (node (ref "F") (pin "L2") (pinfunction "P_L2") (pintype "passive"))
    )
    (net (code "36") (name "CLR_ALL") (class "Default")
      (node (ref "E28") (pin "2") (pinfunction "I0_2") (pintype "input"))
      (node (ref "E28") (pin "9") (pinfunction "I1_9") (pintype "input"))
      (node (ref "H") (pin "D1") (pinfunction "P_D1") (pintype "passive"))
    )
    (net (code "37") (name "CRC1") (class "Default")
      (node (ref "E23") (pin "2") (pinfunction "Q1_2") (pintype "output"))
      (node (ref "E23") (pin "4") (pinfunction "D2_4") (pintype "input"))
    )
    (net (code "38") (name "CRC2") (class "Default")
      (node (ref "E23") (pin "5") (pinfunction "Q2_5") (pintype "output"))
      (node (ref "E24") (pin "5") (pinfunction "I1_5") (pintype "input"))
    )
    (net (code "39") (name "CRC3") (class "Default")
      (node (ref "E14") (pin "9") (pinfunction "SER_9") (pintype "input"))
      (node (ref "E23") (pin "7") (pinfunction "Q3_7") (pintype "output"))
    )
    (net (code "40") (name "CRC4") (class "Default")
      (node (ref "E14") (pin "15") (pinfunction "QA_15") (pintype "output"))
      (node (ref "E16") (pin "2") (pinfunction "I1_2") (pintype "input"))
    )
    (net (code "41") (name "CRC5") (class "Default")
      (node (ref "E14") (pin "14") (pinfunction "QB_14") (pintype "output"))
      (node (ref "E16") (pin "6") (pinfunction "I0_6") (pintype "input"))
    )
    (net (code "42") (name "CRC6") (class "Default")
      (node (ref "E14") (pin "13") (pinfunction "QC_13") (pintype "output"))
      (node (ref "E15") (pin "7") (pinfunction "I1_7") (pintype "input"))
    )
    (net (code "43") (name "CRC7") (class "Default")
      (node (ref "E14") (pin "11") (pinfunction "QD_11") (pintype "output"))
      (node (ref "E15") (pin "2") (pinfunction "I1_2") (pintype "input"))
    )
    (net (code "44") (name "CRC8") (class "Default")
      (node (ref "E14") (pin "10") (pinfunction "QE_10") (pintype "output"))
      (node (ref "E4") (pin "9") (pinfunction "SER_9") (pintype "input"))
      (node (ref "E5") (pin "6") (pinfunction "I0_6") (pintype "input"))
    )
    (net (code "45") (name "CRC9") (class "Default")
      (node (ref "E4") (pin "15") (pinfunction "QA_15") (pintype "output"))
      (node (ref "E6") (pin "2") (pinfunction "I1_2") (pintype "input"))
    )
    (net (code "46") (name "CRC10") (class "Default")
      (node (ref "E4") (pin "14") (pinfunction "QB_14") (pintype "output"))
      (node (ref "E6") (pin "6") (pinfunction "I0_6") (pintype "input"))
    )
    (net (code "47") (name "CRC11") (class "Default")
      (node (ref "E4") (pin "13") (pinfunction "QC_13") (pintype "output"))
      (node (ref "E5") (pin "1") (pinfunction "I0_1") (pintype "input"))
    )
    (net (code "48") (name "CRC12") (class "Default")
      (node (ref "E4") (pin "11") (pinfunction "QD_11") (pintype "output"))
    )
    (net (code "49") (name "CRC13") (class "Default")
      (node (ref "E23") (pin "11") (pinfunction "D4_11") (pintype "input"))
      (node (ref "E4") (pin "10") (pinfunction "QE_10") (pintype "output"))
    )
    (net (code "50") (name "CRC14") (class "Default")
      (node (ref "E23") (pin "10") (pinfunction "Q4_10") (pintype "output"))
      (node (ref "E23") (pin "13") (pinfunction "D5_13") (pintype "input"))
    )
    (net (code "51") (name "CRC15") (class "Default")
      (node (ref "E23") (pin "12") (pinfunction "Q5_12") (pintype "output"))
      (node (ref "E24") (pin "12") (pinfunction "I0_12") (pintype "input"))
    )
    (net (code "52") (name "CRC16") (class "Default")
      (node (ref "E") (pin "N2") (pinfunction "P_N2") (pintype "passive"))
      (node (ref "E23") (pin "15") (pinfunction "Q6_15") (pintype "output"))
      (node (ref "E24") (pin "10") (pinfunction "I1_10") (pintype "input"))
      (node (ref "E9") (pin "13") (pinfunction "I13_13") (pintype "input"))
    )
    (net (code "53") (name "CRC_DATA") (class "Default")
      (node (ref "E") (pin "A1") (pinfunction "P_A1") (pintype "passive"))
      (node (ref "E24") (pin "9") (pinfunction "I0_9") (pintype "input"))
    )
    (net (code "54") (name "DATA_CLK_OK") (class "Default")
      (node (ref "F") (pin "M1") (pinfunction "P_M1") (pintype "passive"))
      (node (ref "H") (pin "C1") (pinfunction "P_C1") (pintype "passive"))
    )
    (net (code "55") (name "DATA_ENABLE") (class "Default")
      (node (ref "E") (pin "U1") (pinfunction "P_U1") (pintype "passive"))
      (node (ref "E1") (pin "11") (pinfunction "I0_11") (pintype "input"))
      (node (ref "E1") (pin "3") (pinfunction "I1_3") (pintype "input"))
      (node (ref "E1") (pin "6") (pinfunction "I1_6") (pintype "input"))
      (node (ref "E1") (pin "8") (pinfunction "I0_8") (pintype "input"))
      (node (ref "E26") (pin "2") (pinfunction "I0_2") (pintype "input"))
      (node (ref "E26") (pin "3") (pinfunction "I1_3") (pintype "input"))
      (node (ref "E26") (pin "5") (pinfunction "I0_5") (pintype "input"))
      (node (ref "E26") (pin "6") (pinfunction "I1_6") (pintype "input"))
      (node (ref "E34") (pin "2") (pinfunction "D_2") (pintype "input"))
      (node (ref "E37") (pin "9") (pinfunction "I0_9") (pintype "input"))
      (node (ref "E39") (pin "9") (pinfunction "Q_9") (pintype "output"))
      (node (ref "E40") (pin "13") (pinfunction "I1_13") (pintype "input"))
      (node (ref "H") (pin "N1") (pinfunction "P_N1") (pintype "passive"))
    )
    (net (code "56") (name "DB_CONT4") (class "Default")
      (node (ref "E37") (pin "3") (pinfunction "I0_3") (pintype "input"))
      (node (ref "H") (pin "E2") (pinfunction "P_E2") (pintype "passive"))
    )
    (net (code "57") (name "DEVICE_RK") (class "Default")
      (node (ref "E38") (pin "2") (pinfunction "I0_2") (pintype "input"))
      (node (ref "E38") (pin "3") (pinfunction "I1_3") (pintype "input"))
      (node (ref "J") (pin "A1") (pinfunction "P_A1") (pintype "passive"))
    )
    (net (code "58") (name "DISK_PRIORITY") (class "Default")
      (node (ref "E33") (pin "1") (pinfunction "I0_1") (pintype "input"))
      (node (ref "E42") (pin "6") (pinfunction "O_6") (pintype "output"))
    )
    (net (code "59") (name "DRIVE_STATUS_BAD") (class "Default")
      (node (ref "E19") (pin "11") (pinfunction "O_11") (pintype "output"))
      (node (ref "J") (pin "H2") (pinfunction "P_H2") (pintype "passive"))
    )
    (net (code "60") (name "DRV_REVO") (class "Default")
      (node (ref "F") (pin "C2") (pinfunction "P_C2") (pintype "passive"))
      (node (ref "J") (pin "K2") (pinfunction "P_K2") (pintype "passive"))
    )
    (net (code "61") (name "EMA0") (class "Default")
      (node (ref "E1") (pin "9") (pinfunction "I1_9") (pintype "input"))
      (node (ref "E3") (pin "9") (pinfunction "Q2_9") (pintype "output"))
    )
    (net (code "62") (name "EMA1") (class "Default")
      (node (ref "E1") (pin "5") (pinfunction "I0_5") (pintype "input"))
      (node (ref "E17") (pin "4") (pinfunction "D_4") (pintype "input"))
      (node (ref "E3") (pin "11") (pinfunction "Q3_11") (pintype "output"))
    )
    (net (code "63") (name "EMA2") (class "Default")
      (node (ref "E1") (pin "2") (pinfunction "I0_2") (pintype "input"))
      (node (ref "E17") (pin "5") (pinfunction "Q0_5") (pintype "output"))
    )
    (net (code "64") (name "ENAB_INT") (class "Default")
      (node (ref "E2") (pin "11") (pinfunction "Q3_11") (pintype "output"))
      (node (ref "E3") (pin "4") (pinfunction "D_4") (pintype "input"))
      (node (ref "J") (pin "B1") (pinfunction "P_B1") (pintype "passive"))
    )
    (net (code "65") (name "ENAB_SEEK_DONE") (class "Default")
      (node (ref "E3") (pin "5") (pinfunction "Q0_5") (pintype "output"))
      (node (ref "J") (pin "S1") (pinfunction "P_S1") (pintype "passive"))
    )
    (net (code "66") (name "EXT_CYL_ADDRS") (class "Default")
      (node (ref "E14") (pin "2") (pinfunction "A_2") (pintype "input"))
      (node (ref "E17") (pin "11") (pinfunction "Q3_11") (pintype "output"))
      (node (ref "E9") (pin "1") (pinfunction "I1_1") (pintype "input"))
    )
    (net (code "67") (name "FILE_RDY") (class "Default")
      (node (ref "E") (pin "E1") (pinfunction "P_E1") (pintype "passive"))
      (node (ref "E19") (pin "12") (pinfunction "I0_12") (pintype "input"))
    )
    (net (code "68") (name "FUNCTION00") (class "Default")
      (node (ref "E") (pin "U2") (pinfunction "P_U2") (pintype "passive"))
      (node (ref "E2") (pin "5") (pinfunction "Q0_5") (pintype "output"))
    )
    (net (code "69") (name "FUNCTION01") (class "Default")
      (node (ref "E") (pin "V2") (pinfunction "P_V2") (pintype "passive"))
      (node (ref "E2") (pin "7") (pinfunction "Q1_7") (pintype "output"))
    )
    (net (code "70") (name "FUNCTION02") (class "Default")
      (node (ref "E") (pin "T2") (pinfunction "P_T2") (pintype "passive"))
      (node (ref "E2") (pin "9") (pinfunction "Q2_9") (pintype "output"))
    )
    (net (code "71") (name "GND") (class "Default")
      (node (ref "C1") (pin "2") (pinfunction "2_2") (pintype "passive"))
      (node (ref "C10") (pin "2") (pinfunction "2_2") (pintype "passive"))
      (node (ref "C11") (pin "2") (pinfunction "2_2") (pintype "passive"))
      (node (ref "C12") (pin "2") (pinfunction "2_2") (pintype "passive"))
      (node (ref "C13") (pin "2") (pinfunction "2_2") (pintype "passive"))
      (node (ref "C14") (pin "2") (pinfunction "2_2") (pintype "passive"))
      (node (ref "C15") (pin "2") (pinfunction "2_2") (pintype "passive"))
      (node (ref "C16") (pin "2") (pinfunction "2_2") (pintype "passive"))
      (node (ref "C17") (pin "2") (pinfunction "2_2") (pintype "passive"))
      (node (ref "C18") (pin "2") (pinfunction "2_2") (pintype "passive"))
      (node (ref "C19") (pin "2") (pinfunction "2_2") (pintype "passive"))
      (node (ref "C2") (pin "2") (pinfunction "2_2") (pintype "passive"))
      (node (ref "C20") (pin "2") (pinfunction "2_2") (pintype "passive"))
      (node (ref "C21") (pin "2") (pinfunction "2_2") (pintype "passive"))
      (node (ref "C22") (pin "2") (pinfunction "2_2") (pintype "passive"))
      (node (ref "C23") (pin "2") (pinfunction "2_2") (pintype "passive"))
      (node (ref "C24") (pin "2") (pinfunction "2_2") (pintype "passive"))
      (node (ref "C25") (pin "2") (pinfunction "2_2") (pintype "passive"))
      (node (ref "C26") (pin "2") (pinfunction "2_2") (pintype "passive"))
      (node (ref "C27") (pin "2") (pinfunction "2_2") (pintype "passive"))
      (node (ref "C28") (pin "2") (pinfunction "2_2") (pintype "passive"))
      (node (ref "C29") (pin "2") (pinfunction "2_2") (pintype "passive"))
      (node (ref "C3") (pin "2") (pinfunction "2_2") (pintype "passive"))
      (node (ref "C30") (pin "2") (pinfunction "2_2") (pintype "passive"))
      (node (ref "C31") (pin "2") (pinfunction "2_2") (pintype "passive"))
      (node (ref "C32") (pin "2") (pinfunction "2_2") (pintype "passive"))
      (node (ref "C33") (pin "2") (pinfunction "2_2") (pintype "passive"))
      (node (ref "C34") (pin "-") (pinfunction "-_-") (pintype "passive"))
      (node (ref "C35") (pin "-") (pinfunction "-_-") (pintype "passive"))
      (node (ref "C36") (pin "-") (pinfunction "-_-") (pintype "passive"))
      (node (ref "C37") (pin "2") (pinfunction "2_2") (pintype "passive"))
      (node (ref "C4") (pin "2") (pinfunction "2_2") (pintype "passive"))
      (node (ref "C5") (pin "2") (pinfunction "2_2") (pintype "passive"))
      (node (ref "C6") (pin "2") (pinfunction "2_2") (pintype "passive"))
      (node (ref "C7") (pin "2") (pinfunction "2_2") (pintype "passive"))
      (node (ref "C8") (pin "2") (pinfunction "2_2") (pintype "passive"))
      (node (ref "C9") (pin "2") (pinfunction "2_2") (pintype "passive"))
      (node (ref "E2") (pin "4") (pinfunction "D_4") (pintype "input"))
      (node (ref "E27") (pin "5") (pinfunction "I1_5") (pintype "input"))
      (node (ref "E27") (pin "6") (pinfunction "I0_6") (pintype "input"))
      (node (ref "E32") (pin "11") (pinfunction "I0_11") (pintype "input"))
      (node (ref "E32") (pin "5") (pinfunction "I1_5") (pintype "input"))
      (node (ref "E32") (pin "6") (pinfunction "I0_6") (pintype "input"))
      (node (ref "E32") (pin "9") (pinfunction "I0_9") (pintype "input"))
      (node (ref "E4") (pin "6") (pinfunction "D_6") (pintype "input"))
      (node (ref "E4") (pin "7") (pinfunction "E_7") (pintype "input"))
      (node (ref "E42") (pin "1") (pinfunction "I_1") (pintype "input"))
      (node (ref "E48") (pin "12") (pinfunction "D_12") (pintype "input"))
      (node (ref "E48") (pin "2") (pinfunction "D_2") (pintype "input"))
      (node (ref "E9") (pin "3") (pinfunction "I3_3") (pintype "input"))
      (node (ref "E9") (pin "4") (pinfunction "I4_4") (pintype "input"))
      (node (ref "E9") (pin "5") (pinfunction "I5_5") (pintype "input"))
      (node (ref "OMNIBUS") (pin "AC2") (pinfunction "1_AC2") (pintype "bidirectional"))
      (node (ref "OMNIBUS") (pin "AF1") (pinfunction "1_AF1") (pintype "bidirectional"))
      (node (ref "OMNIBUS") (pin "AF2") (pinfunction "1_AF2") (pintype "bidirectional"))
      (node (ref "OMNIBUS") (pin "AN1") (pinfunction "1_AN1") (pintype "bidirectional"))
      (node (ref "OMNIBUS") (pin "AN2") (pinfunction "1_AN2") (pintype "bidirectional"))
      (node (ref "OMNIBUS") (pin "AT1") (pinfunction "1_AT1") (pintype "bidirectional"))
      (node (ref "OMNIBUS") (pin "AT2") (pinfunction "1_AT2") (pintype "bidirectional"))
      (node (ref "OMNIBUS") (pin "BC1") (pinfunction "1_BC1") (pintype "bidirectional"))
      (node (ref "OMNIBUS") (pin "BC2") (pinfunction "1_BC2") (pintype "bidirectional"))
      (node (ref "OMNIBUS") (pin "BF1") (pinfunction "1_BF1") (pintype "bidirectional"))
      (node (ref "OMNIBUS") (pin "BF2") (pinfunction "1_BF2") (pintype "bidirectional"))
      (node (ref "OMNIBUS") (pin "BN1") (pinfunction "1_BN1") (pintype "bidirectional"))
      (node (ref "OMNIBUS") (pin "BN2") (pinfunction "1_BN2") (pintype "bidirectional"))
      (node (ref "OMNIBUS") (pin "BT1") (pinfunction "1_BT1") (pintype "bidirectional"))
      (node (ref "OMNIBUS") (pin "BT2") (pinfunction "1_BT2") (pintype "bidirectional"))
      (node (ref "OMNIBUS") (pin "CC1") (pinfunction "1_CC1") (pintype "bidirectional"))
      (node (ref "OMNIBUS") (pin "CC2") (pinfunction "1_CC2") (pintype "bidirectional"))
      (node (ref "OMNIBUS") (pin "CF1") (pinfunction "1_CF1") (pintype "bidirectional"))
      (node (ref "OMNIBUS") (pin "CF2") (pinfunction "1_CF2") (pintype "bidirectional"))
      (node (ref "OMNIBUS") (pin "CN1") (pinfunction "1_CN1") (pintype "bidirectional"))
      (node (ref "OMNIBUS") (pin "CN2") (pinfunction "1_CN2") (pintype "bidirectional"))
      (node (ref "OMNIBUS") (pin "CT1") (pinfunction "1_CT1") (pintype "bidirectional"))
      (node (ref "OMNIBUS") (pin "CT2") (pinfunction "1_CT2") (pintype "bidirectional"))
      (node (ref "OMNIBUS") (pin "DC1") (pinfunction "1_DC1") (pintype "bidirectional"))
      (node (ref "OMNIBUS") (pin "DC2") (pinfunction "1_DC2") (pintype "bidirectional"))
      (node (ref "OMNIBUS") (pin "DF1") (pinfunction "1_DF1") (pintype "bidirectional"))
      (node (ref "OMNIBUS") (pin "DF2") (pinfunction "1_DF2") (pintype "bidirectional"))
      (node (ref "OMNIBUS") (pin "DN1") (pinfunction "1_DN1") (pintype "bidirectional"))
      (node (ref "OMNIBUS") (pin "DN2") (pinfunction "1_DN2") (pintype "bidirectional"))
      (node (ref "OMNIBUS") (pin "DT1") (pinfunction "1_DT1") (pintype "bidirectional"))
      (node (ref "OMNIBUS") (pin "DT2") (pinfunction "1_DT2") (pintype "bidirectional"))
      (node (ref "R1") (pin "1") (pinfunction "1_1") (pintype "passive"))
      (node (ref "R11") (pin "1") (pinfunction "1_1") (pintype "passive"))
      (node (ref "R13") (pin "1") (pinfunction "1_1") (pintype "passive"))
      (node (ref "R14") (pin "1") (pinfunction "1_1") (pintype "passive"))
      (node (ref "R17") (pin "1") (pinfunction "1_1") (pintype "passive"))
      (node (ref "R18") (pin "1") (pinfunction "1_1") (pintype "passive"))
      (node (ref "R21") (pin "1") (pinfunction "1_1") (pintype "passive"))
      (node (ref "R22") (pin "1") (pinfunction "1_1") (pintype "passive"))
      (node (ref "R25") (pin "1") (pinfunction "1_1") (pintype "passive"))
      (node (ref "R26") (pin "1") (pinfunction "1_1") (pintype "passive"))
      (node (ref "R3") (pin "1") (pinfunction "1_1") (pintype "passive"))
      (node (ref "R4") (pin "1") (pinfunction "1_1") (pintype "passive"))
      (node (ref "R7") (pin "1") (pinfunction "1_1") (pintype "passive"))
      (node (ref "R8") (pin "1") (pinfunction "1_1") (pintype "passive"))
      (node (ref "W1") (pin "1") (pinfunction "1_1") (pintype "passive"))
    )
    (net (code "72") (name "HALF_BLOCK") (class "Default")
      (node (ref "E") (pin "S2") (pinfunction "P_S2") (pintype "passive"))
      (node (ref "E3") (pin "7") (pinfunction "Q1_7") (pintype "output"))
    )
    (net (code "73") (name "HI_DATA_IN") (class "Default")
      (node (ref "E49") (pin "11") (pinfunction "O_11") (pintype "output"))
      (node (ref "J") (pin "R2") (pinfunction "P_R2") (pintype "passive"))
    )
    (net (code "74") (name "HI_RD_CLK") (class "Default")
      (node (ref "E49") (pin "8") (pinfunction "O_8") (pintype "output"))
      (node (ref "J") (pin "M1") (pinfunction "P_M1") (pintype "passive"))
    )
    (net (code "75") (name "IDLE") (class "Default")
      (node (ref "E") (pin "C1") (pinfunction "P_C1") (pintype "passive"))
      (node (ref "E19") (pin "2") (pinfunction "I1_2") (pintype "input"))
      (node (ref "J") (pin "L2") (pinfunction "P_L2") (pintype "passive"))
    )
    (net (code "76") (name "INT_STROBE") (class "Default")
      (node (ref "E27") (pin "7") (pinfunction "I1_7") (pintype "input"))
      (node (ref "OMNIBUS") (pin "BD2") (pinfunction "1_BD2") (pintype "bidirectional"))
    )
    (net (code "77") (name "LAST_BRK") (class "Default")
      (node (ref "E45") (pin "9") (pinfunction "Q_9") (pintype "output"))
      (node (ref "F") (pin "N2") (pinfunction "P_N2") (pintype "passive"))
    )
    (net (code "78") (name "LAST_WORD_PL") (class "Default")
      (node (ref "F") (pin "E1") (pinfunction "P_E1") (pintype "passive"))
      (node (ref "J") (pin "N2") (pinfunction "P_N2") (pintype "passive"))
    )
    (net (code "79") (name "LD_CMD_REG") (class "Default")
      (node (ref "E10") (pin "2") (pinfunction "1G_2") (pintype "input"))
      (node (ref "E41") (pin "6") (pinfunction "O_6") (pintype "output"))
      (node (ref "E47") (pin "6") (pinfunction "I1_6") (pintype "input"))
      (node (ref "J") (pin "P1") (pinfunction "P_P1") (pintype "passive"))
    )
    (net (code "80") (name "LD_DISK_ADDRS") (class "Default")
      (node (ref "E") (pin "M2") (pinfunction "P_M2") (pintype "passive"))
      (node (ref "E14") (pin "8") (pinfunction "PE_8") (pintype "input"))
      (node (ref "E28") (pin "8") (pinfunction "I0_8") (pintype "input"))
      (node (ref "E4") (pin "8") (pinfunction "PE_8") (pintype "input"))
      (node (ref "J") (pin "B2") (pinfunction "P_B2") (pintype "passive"))
    )
    (net (code "81") (name "LO_MAIN_DATA") (class "Default")
      (node (ref "E30") (pin "8") (pinfunction "O_8") (pintype "output"))
      (node (ref "H") (pin "V2") (pinfunction "P_V2") (pintype "passive"))
    )
    (net (code "82") (name "MAD") (class "Default")
      (node (ref "E33") (pin "12") (pinfunction "O_12") (pintype "output"))
      (node (ref "E39") (pin "12") (pinfunction "D_12") (pintype "input"))
      (node (ref "E45") (pin "2") (pinfunction "D_2") (pintype "input"))
    )
    (net (code "83") (name "MAIN") (class "Default")
      (node (ref "E30") (pin "10") (pinfunction "I1_10") (pintype "input"))
      (node (ref "E30") (pin "5") (pinfunction "I1_5") (pintype "input"))
      (node (ref "E39") (pin "5") (pinfunction "Q_5") (pintype "output"))
      (node (ref "E40") (pin "10") (pinfunction "I1_10") (pintype "input"))
      (node (ref "H") (pin "A2") (pinfunction "P_A2") (pintype "passive"))
    )
    (net (code "84") (name "MAIN_DATA") (class "Default")
      (node (ref "E40") (pin "1") (pinfunction "I0_1") (pintype "input"))
      (node (ref "E47") (pin "10") (pinfunction "O_10") (pintype "output"))
      (node (ref "E49") (pin "1") (pinfunction "I0_1") (pintype "input"))
    )
    (net (code "85") (name "MAIN_ENAB") (class "Default")
      (node (ref "E25") (pin "4") (pinfunction "I0_4") (pintype "input"))
      (node (ref "E30") (pin "6") (pinfunction "O_6") (pintype "output"))
      (node (ref "E37") (pin "2") (pinfunction "I1_2") (pintype "input"))
    )
    (net (code "86") (name "MAIN_PL") (class "Default")
      (node (ref "E25") (pin "12") (pinfunction "I0_12") (pintype "input"))
      (node (ref "E25") (pin "6") (pinfunction "O_6") (pintype "output"))
      (node (ref "E31") (pin "4") (pinfunction "I0_4") (pintype "input"))
      (node (ref "E36") (pin "12") (pinfunction "I0_12") (pintype "input"))
      (node (ref "E40") (pin "5") (pinfunction "I1_5") (pintype "input"))
      (node (ref "E41") (pin "1") (pinfunction "I0_1") (pintype "input"))
      (node (ref "H") (pin "T1") (pinfunction "P_T1") (pintype "passive"))
    )
    (net (code "87") (name "MAK") (class "Default")
      (node (ref "E20") (pin "11") (pinfunction "I0_11") (pintype "input"))
      (node (ref "E20") (pin "2") (pinfunction "I0_2") (pintype "input"))
      (node (ref "E20") (pin "6") (pinfunction "I1_6") (pintype "input"))
      (node (ref "E20") (pin "8") (pinfunction "I0_8") (pintype "input"))
      (node (ref "E40") (pin "9") (pinfunction "I0_9") (pintype "input"))
      (node (ref "E44") (pin "11") (pinfunction "I0_11") (pintype "input"))
      (node (ref "E44") (pin "3") (pinfunction "I1_3") (pintype "input"))
      (node (ref "E44") (pin "6") (pinfunction "I1_6") (pintype "input"))
      (node (ref "E44") (pin "9") (pinfunction "I1_9") (pintype "input"))
      (node (ref "E45") (pin "5") (pinfunction "Q_5") (pintype "output"))
      (node (ref "E7") (pin "11") (pinfunction "I0_11") (pintype "input"))
      (node (ref "E7") (pin "3") (pinfunction "I1_3") (pintype "input"))
      (node (ref "E7") (pin "6") (pinfunction "I1_6") (pintype "input"))
      (node (ref "E7") (pin "8") (pinfunction "I0_8") (pintype "input"))
    )
    (net (code "88") (name "MALC") (class "Default")
      (node (ref "E26") (pin "11") (pinfunction "I0_11") (pintype "input"))
      (node (ref "E26") (pin "12") (pinfunction "I1_12") (pintype "input"))
      (node (ref "E34") (pin "5") (pinfunction "Q_5") (pintype "output"))
    )
    (net (code "89") (name "MUX_INPUT") (class "Default")
      (node (ref "E29") (pin "5") (pinfunction "I1_5") (pintype "input"))
      (node (ref "E31") (pin "11") (pinfunction "O_11") (pintype "output"))
    )
    (net (code "90") (name "NBR") (class "Default")
      (node (ref "E26") (pin "8") (pinfunction "I0_8") (pintype "input"))
      (node (ref "E26") (pin "9") (pinfunction "I1_9") (pintype "input"))
      (node (ref "E33") (pin "2") (pinfunction "I1_2") (pintype "input"))
      (node (ref "E35") (pin "9") (pinfunction "Q_9") (pintype "output"))
      (node (ref "E38") (pin "11") (pinfunction "I0_11") (pintype "input"))
      (node (ref "E38") (pin "8") (pinfunction "I0_8") (pintype "input"))
      (node (ref "E38") (pin "9") (pinfunction "I1_9") (pintype "input"))
    )
    (net (code "91") (name "NOT_EQUAL") (class "Default")
      (node (ref "E34") (pin "9") (pinfunction "Q_9") (pintype "output"))
    )
    (net (code "92") (name "Net-(E7A-I0)") (class "Default")
      (node (ref "E7") (pin "2") (pinfunction "I0_2") (pintype "input"))
      (node (ref "E8") (pin "14") (pinfunction "QA_14") (pintype "output"))
    )
    (net (code "93") (name "Net-(E7B-I0)") (class "Default")
      (node (ref "E7") (pin "5") (pinfunction "I0_5") (pintype "input"))
      (node (ref "E8") (pin "13") (pinfunction "QB_13") (pintype "output"))
    )
    (net (code "94") (name "Net-(E7C-I1)") (class "Default")
      (node (ref "E7") (pin "9") (pinfunction "I1_9") (pintype "input"))
      (node (ref "E8") (pin "12") (pinfunction "QC_12") (pintype "output"))
    )
    (net (code "95") (name "Net-(E7D-I1)") (class "Default")
      (node (ref "E7") (pin "12") (pinfunction "I1_12") (pintype "input"))
      (node (ref "E8") (pin "11") (pinfunction "QD_11") (pintype "output"))
    )
    (net (code "96") (name "Net-(E14A-CLK)") (class "Default")
      (node (ref "E14") (pin "1") (pinfunction "CLK_1") (pintype "input"))
      (node (ref "E23") (pin "9") (pinfunction "CLK_9") (pintype "input"))
      (node (ref "E31") (pin "8") (pinfunction "O_8") (pintype "output"))
      (node (ref "E4") (pin "1") (pinfunction "CLK_1") (pintype "input"))
    )
    (net (code "97") (name "Net-(E18A-CLK)") (class "Default")
      (node (ref "E18") (pin "2") (pinfunction "CLK_2") (pintype "input"))
      (node (ref "E21") (pin "2") (pinfunction "CLK_2") (pintype "input"))
      (node (ref "E28") (pin "13") (pinfunction "O_13") (pintype "output"))
      (node (ref "E8") (pin "2") (pinfunction "CLK_2") (pintype "input"))
    )
    (net (code "98") (name "Net-(E18A-QA)") (class "Default")
      (node (ref "E18") (pin "14") (pinfunction "QA_14") (pintype "output"))
      (node (ref "E44") (pin "12") (pinfunction "I1_12") (pintype "input"))
    )
    (net (code "99") (name "Net-(E18A-QB)") (class "Default")
      (node (ref "E18") (pin "13") (pinfunction "QB_13") (pintype "output"))
      (node (ref "E44") (pin "2") (pinfunction "I0_2") (pintype "input"))
    )
    (net (code "100") (name "Net-(E18A-QC)") (class "Default")
      (node (ref "E18") (pin "12") (pinfunction "QC_12") (pintype "output"))
      (node (ref "E44") (pin "5") (pinfunction "I0_5") (pintype "input"))
    )
    (net (code "101") (name "Net-(E18A-QD)") (class "Default")
      (node (ref "E18") (pin "11") (pinfunction "QD_11") (pintype "output"))
      (node (ref "E44") (pin "8") (pinfunction "I0_8") (pintype "input"))
    )
    (net (code "102") (name "Net-(E18A-RCO)") (class "Default")
      (node (ref "E18") (pin "15") (pinfunction "RCO_15") (pintype "output"))
      (node (ref "E21") (pin "10") (pinfunction "ENT_10") (pintype "input"))
      (node (ref "E21") (pin "7") (pinfunction "ENP_7") (pintype "input"))
    )
    (net (code "103") (name "Net-(E19A-I0)") (class "Default")
      (node (ref "E19") (pin "1") (pinfunction "I0_1") (pintype "input"))
      (node (ref "E24") (pin "3") (pinfunction "O_3") (pintype "output"))
    )
    (net (code "104") (name "Net-(E20A-I1)") (class "Default")
      (node (ref "E20") (pin "3") (pinfunction "I1_3") (pintype "input"))
      (node (ref "E21") (pin "14") (pinfunction "QA_14") (pintype "output"))
    )
    (net (code "105") (name "Net-(E20B-I0)") (class "Default")
      (node (ref "E20") (pin "5") (pinfunction "I0_5") (pintype "input"))
      (node (ref "E21") (pin "13") (pinfunction "QB_13") (pintype "output"))
    )
    (net (code "106") (name "Net-(E20C-I1)") (class "Default")
      (node (ref "E20") (pin "9") (pinfunction "I1_9") (pintype "input"))
      (node (ref "E21") (pin "11") (pinfunction "QD_11") (pintype "output"))
    )
    (net (code "107") (name "Net-(E20D-I1)") (class "Default")
      (node (ref "E20") (pin "12") (pinfunction "I1_12") (pintype "input"))
      (node (ref "E21") (pin "12") (pinfunction "QC_12") (pintype "output"))
    )
    (net (code "108") (name "Net-(E21A-RCO)") (class "Default")
      (node (ref "E21") (pin "15") (pinfunction "RCO_15") (pintype "output"))
      (node (ref "E8") (pin "10") (pinfunction "ENT_10") (pintype "input"))
      (node (ref "E8") (pin "7") (pinfunction "ENP_7") (pintype "input"))
    )
    (net (code "109") (name "Net-(E23A-D1)") (class "Default")
      (node (ref "E23") (pin "3") (pinfunction "D1_3") (pintype "input"))
      (node (ref "E29") (pin "8") (pinfunction "O_8") (pintype "output"))
    )
    (net (code "110") (name "Net-(E23A-D3)") (class "Default")
      (node (ref "E23") (pin "6") (pinfunction "D3_6") (pintype "input"))
      (node (ref "E24") (pin "6") (pinfunction "O_6") (pintype "output"))
    )
    (net (code "111") (name "Net-(E23A-D6)") (class "Default")
      (node (ref "E23") (pin "14") (pinfunction "D6_14") (pintype "input"))
      (node (ref "E24") (pin "11") (pinfunction "O_11") (pintype "output"))
    )
    (net (code "112") (name "Net-(E24B-I0)") (class "Default")
      (node (ref "E24") (pin "4") (pinfunction "I0_4") (pintype "input"))
      (node (ref "E30") (pin "3") (pinfunction "O_3") (pintype "output"))
    )
    (net (code "113") (name "Net-(E24C-O)") (class "Default")
      (node (ref "E24") (pin "8") (pinfunction "O_8") (pintype "output"))
      (node (ref "E29") (pin "2") (pinfunction "I1_2") (pintype "input"))
      (node (ref "E30") (pin "12") (pinfunction "I0_12") (pintype "input"))
      (node (ref "E30") (pin "2") (pinfunction "I1_2") (pintype "input"))
      (node (ref "E34") (pin "12") (pinfunction "D_12") (pintype "input"))
    )
    (net (code "114") (name "Net-(E24D-I1)") (class "Default")
      (node (ref "E24") (pin "13") (pinfunction "I1_13") (pintype "input"))
      (node (ref "E30") (pin "11") (pinfunction "O_11") (pintype "output"))
    )
    (net (code "115") (name "Net-(E25A-O)") (class "Default")
      (node (ref "E25") (pin "3") (pinfunction "O_3") (pintype "output"))
      (node (ref "E34") (pin "13") (pinfunction "CLR_13") (pintype "input"))
    )
    (net (code "116") (name "Net-(E25C-O)") (class "Default")
      (node (ref "E25") (pin "8") (pinfunction "O_8") (pintype "output"))
      (node (ref "E34") (pin "11") (pinfunction "CLK_11") (pintype "input"))
    )
    (net (code "117") (name "Net-(E28A-O)") (class "Default")
      (node (ref "E28") (pin "1") (pinfunction "O_1") (pintype "output"))
      (node (ref "E35") (pin "13") (pinfunction "CLR_13") (pintype "input"))
    )
    (net (code "118") (name "Net-(E28B-I0)") (class "Default")
      (node (ref "E28") (pin "5") (pinfunction "I0_5") (pintype "input"))
      (node (ref "E40") (pin "11") (pinfunction "O_11") (pintype "output"))
    )
    (net (code "119") (name "Net-(E28B-O)") (class "Default")
      (node (ref "E28") (pin "11") (pinfunction "I0_11") (pintype "input"))
      (node (ref "E28") (pin "4") (pinfunction "O_4") (pintype "output"))
    )
    (net (code "120") (name "Net-(E28D-I1)") (class "Default")
      (node (ref "E28") (pin "12") (pinfunction "I1_12") (pintype "input"))
      (node (ref "E41") (pin "8") (pinfunction "O_8") (pintype "output"))
    )
    (net (code "121") (name "Net-(E29A-O)") (class "Default")
      (node (ref "E29") (pin "10") (pinfunction "I1_10") (pintype "input"))
      (node (ref "E29") (pin "3") (pinfunction "O_3") (pintype "output"))
    )
    (net (code "122") (name "Net-(E29B-O)") (class "Default")
      (node (ref "E29") (pin "6") (pinfunction "O_6") (pintype "output"))
      (node (ref "E29") (pin "9") (pinfunction "I0_9") (pintype "input"))
    )
    (net (code "123") (name "Net-(E29D-I0)") (class "Default")
      (node (ref "E29") (pin "12") (pinfunction "I0_12") (pintype "input"))
      (node (ref "E43") (pin "1") (pinfunction "I_1") (pintype "input"))
      (node (ref "E49") (pin "6") (pinfunction "O_6") (pintype "output"))
    )
    (net (code "124") (name "Net-(E29D-I1)") (class "Default")
      (node (ref "C37") (pin "1") (pinfunction "1_1") (pintype "passive"))
      (node (ref "E29") (pin "13") (pinfunction "I1_13") (pintype "input"))
      (node (ref "R30") (pin "2") (pinfunction "2_2") (pintype "passive"))
    )
    (net (code "125") (name "Net-(E30C-I0)") (class "Default")
      (node (ref "E30") (pin "9") (pinfunction "I0_9") (pintype "input"))
      (node (ref "E9") (pin "8") (pinfunction "O8_8") (pintype "output"))
    )
    (net (code "126") (name "Net-(E31A-I0)") (class "Default")
      (node (ref "E31") (pin "1") (pinfunction "I0_1") (pintype "input"))
      (node (ref "E47") (pin "1") (pinfunction "O_1") (pintype "output"))
    )
    (net (code "127") (name "Net-(E31A-O)") (class "Default")
      (node (ref "E31") (pin "3") (pinfunction "O_3") (pintype "output"))
      (node (ref "E31") (pin "5") (pinfunction "I1_5") (pintype "input"))
    )
    (net (code "128") (name "Net-(E32D-I1)") (class "Default")
      (node (ref "E32") (pin "12") (pinfunction "I1_12") (pintype "input"))
      (node (ref "W3") (pin "2") (pinfunction "2_2") (pintype "passive"))
    )
    (net (code "129") (name "Net-(E32D-O)") (class "Default")
      (node (ref "E32") (pin "13") (pinfunction "O_13") (pintype "output"))
      (node (ref "W2") (pin "1") (pinfunction "1_1") (pintype "passive"))
    )
    (net (code "130") (name "Net-(E33C-I1)") (class "Default")
      (node (ref "E33") (pin "10") (pinfunction "I1_10") (pintype "input"))
      (node (ref "E36") (pin "3") (pinfunction "O_3") (pintype "output"))
    )
    (net (code "131") (name "Net-(E33C-O)") (class "Default")
      (node (ref "E33") (pin "8") (pinfunction "O_8") (pintype "output"))
      (node (ref "E39") (pin "11") (pinfunction "CLK_11") (pintype "input"))
      (node (ref "E45") (pin "3") (pinfunction "CLK_3") (pintype "input"))
    )
    (net (code "132") (name "Net-(E36C-O)") (class "Default")
      (node (ref "E36") (pin "8") (pinfunction "O_8") (pintype "output"))
      (node (ref "E48") (pin "13") (pinfunction "CLR_13") (pintype "input"))
    )
    (net (code "133") (name "Net-(E40C-O)") (class "Default")
      (node (ref "E40") (pin "8") (pinfunction "O_8") (pintype "output"))
      (node (ref "E41") (pin "12") (pinfunction "I0_12") (pintype "input"))
    )
    (net (code "134") (name "Net-(E41C-I0)") (class "Default")
      (node (ref "E41") (pin "9") (pinfunction "I0_9") (pintype "input"))
      (node (ref "E47") (pin "13") (pinfunction "O_13") (pintype "output"))
    )
    (net (code "135") (name "Net-(E41D-O)") (class "Default")
      (node (ref "E41") (pin "11") (pinfunction "O_11") (pintype "output"))
      (node (ref "E48") (pin "4") (pinfunction "PRE_4") (pintype "input"))
    )
    (net (code "136") (name "Net-(E42C-I)") (class "Default")
      (node (ref "E42") (pin "5") (pinfunction "I_5") (pintype "input"))
      (node (ref "W1") (pin "2") (pinfunction "2_2") (pintype "passive"))
      (node (ref "W2") (pin "2") (pinfunction "2_2") (pintype "passive"))
    )
    (net (code "137") (name "Net-(E43A-O)") (class "Default")
      (node (ref "E43") (pin "2") (pinfunction "O_2") (pintype "output"))
      (node (ref "R30") (pin "1") (pinfunction "1_1") (pintype "passive"))
    )
    (net (code "138") (name "Net-(E43B-O)") (class "Default")
      (node (ref "E43") (pin "4") (pinfunction "O_4") (pintype "output"))
      (node (ref "E45") (pin "11") (pinfunction "CLK_11") (pintype "input"))
    )
    (net (code "139") (name "PRIORITY") (class "Default")
      (node (ref "E38") (pin "13") (pinfunction "O_13") (pintype "open_collector"))
      (node (ref "W4") (pin "1") (pinfunction "1_1") (pintype "passive"))
      (node (ref "W5") (pin "2") (pinfunction "2_2") (pintype "passive"))
    )
    (net (code "140") (name "RDY_S{slash}R{slash}W") (class "Default")
      (node (ref "E") (pin "D1") (pinfunction "P_D1") (pintype "passive"))
      (node (ref "E19") (pin "13") (pinfunction "I1_13") (pintype "input"))
      (node (ref "E32") (pin "14") (pinfunction "O_14") (pintype "output"))
      (node (ref "E43") (pin "9") (pinfunction "I_9") (pintype "input"))
      (node (ref "R31") (pin "1") (pinfunction "1_1") (pintype "passive"))
    )
    (net (code "141") (name "RDY_S{slash}R{slash}W_SLO") (class "Default")
      (node (ref "J") (pin "L1") (pinfunction "P_L1") (pintype "passive"))
      (node (ref "R31") (pin "2") (pinfunction "2_2") (pintype "passive"))
    )
    (net (code "142") (name "RD_CLK1") (class "Default")
      (node (ref "E") (pin "B1") (pinfunction "P_B1") (pintype "passive"))
      (node (ref "E25") (pin "9") (pinfunction "I0_9") (pintype "input"))
    )
    (net (code "143") (name "RK_DATA11") (class "Default")
      (node (ref "F") (pin "H1") (pinfunction "P_H1") (pintype "passive"))
      (node (ref "H") (pin "F1") (pinfunction "P_F1") (pintype "passive"))
    )
    (net (code "144") (name "SECTOR_ADDRS_1") (class "Default")
      (node (ref "E") (pin "P2") (pinfunction "P_P2") (pintype "passive"))
      (node (ref "E9") (pin "11") (pinfunction "I11_11") (pintype "input"))
    )
    (net (code "145") (name "SEEK_FAIL") (class "Default")
      (node (ref "E42") (pin "4") (pinfunction "O_4") (pintype "output"))
      (node (ref "H") (pin "U2") (pinfunction "P_U2") (pintype "passive"))
    )
    (net (code "146") (name "SET_MAIN_BRK") (class "Default")
      (node (ref "E36") (pin "9") (pinfunction "I0_9") (pintype "input"))
      (node (ref "E42") (pin "12") (pinfunction "O_12") (pintype "output"))
    )
    (net (code "147") (name "SHFT_CMD_REG") (class "Default")
      (node (ref "E41") (pin "3") (pinfunction "O_3") (pintype "output"))
      (node (ref "E47") (pin "5") (pinfunction "I0_5") (pintype "input"))
    )
    (net (code "148") (name "SHFT_SURF") (class "Default")
      (node (ref "E25") (pin "11") (pinfunction "O_11") (pintype "output"))
      (node (ref "F") (pin "U1") (pinfunction "P_U1") (pintype "passive"))
    )
    (net (code "149") (name "STATE_ENAB_B") (class "Default")
      (node (ref "E25") (pin "10") (pinfunction "I1_10") (pintype "input"))
      (node (ref "F") (pin "V1") (pinfunction "P_V1") (pintype "passive"))
    )
    (net (code "150") (name "STROBE") (class "Default")
      (node (ref "E") (pin "F2") (pinfunction "P_F2") (pintype "passive"))
      (node (ref "E15") (pin "1") (pinfunction "I0_1") (pintype "input"))
      (node (ref "E15") (pin "6") (pinfunction "I0_6") (pintype "input"))
      (node (ref "E16") (pin "1") (pinfunction "I0_1") (pintype "input"))
      (node (ref "E16") (pin "7") (pinfunction "I1_7") (pintype "input"))
      (node (ref "E5") (pin "2") (pinfunction "I1_2") (pintype "input"))
      (node (ref "E5") (pin "7") (pinfunction "I1_7") (pintype "input"))
      (node (ref "E6") (pin "1") (pinfunction "I0_1") (pintype "input"))
      (node (ref "E6") (pin "7") (pinfunction "I1_7") (pintype "input"))
    )
    (net (code "151") (name "TP1") (class "Default")
      (node (ref "E27") (pin "4") (pinfunction "I0_4") (pintype "input"))
      (node (ref "OMNIBUS") (pin "CD2") (pinfunction "1_CD2") (pintype "bidirectional"))
    )
    (net (code "152") (name "TP4") (class "Default")
      (node (ref "E33") (pin "5") (pinfunction "I2_5") (pintype "input"))
      (node (ref "OMNIBUS") (pin "CJ2") (pinfunction "1_CJ2") (pintype "bidirectional"))
    )
    (net (code "153") (name "TS2") (class "Default")
      (node (ref "E32") (pin "4") (pinfunction "I0_4") (pintype "input"))
      (node (ref "OMNIBUS") (pin "CL2") (pinfunction "1_CL2") (pintype "bidirectional"))
    )
    (net (code "154") (name "TS4") (class "Default")
      (node (ref "E32") (pin "7") (pinfunction "I1_7") (pintype "input"))
      (node (ref "OMNIBUS") (pin "CP2") (pinfunction "1_CP2") (pintype "bidirectional"))
    )
    (net (code "155") (name "UNIT_SEL0") (class "Default")
      (node (ref "E10") (pin "3") (pinfunction "B_3") (pintype "input"))
      (node (ref "E17") (pin "7") (pinfunction "Q1_7") (pintype "output"))
    )
    (net (code "156") (name "UNIT_SEL1") (class "Default")
      (node (ref "E10") (pin "13") (pinfunction "A_13") (pintype "input"))
      (node (ref "E17") (pin "9") (pinfunction "Q2_9") (pintype "output"))
    )
    (net (code "157") (name "VCC") (class "Default")
      (node (ref "C1") (pin "1") (pinfunction "1_1") (pintype "passive"))
      (node (ref "C10") (pin "1") (pinfunction "1_1") (pintype "passive"))
      (node (ref "C11") (pin "1") (pinfunction "1_1") (pintype "passive"))
      (node (ref "C12") (pin "1") (pinfunction "1_1") (pintype "passive"))
      (node (ref "C13") (pin "1") (pinfunction "1_1") (pintype "passive"))
      (node (ref "C14") (pin "1") (pinfunction "1_1") (pintype "passive"))
      (node (ref "C15") (pin "1") (pinfunction "1_1") (pintype "passive"))
      (node (ref "C16") (pin "1") (pinfunction "1_1") (pintype "passive"))
      (node (ref "C17") (pin "1") (pinfunction "1_1") (pintype "passive"))
      (node (ref "C18") (pin "1") (pinfunction "1_1") (pintype "passive"))
      (node (ref "C19") (pin "1") (pinfunction "1_1") (pintype "passive"))
      (node (ref "C2") (pin "1") (pinfunction "1_1") (pintype "passive"))
      (node (ref "C20") (pin "1") (pinfunction "1_1") (pintype "passive"))
      (node (ref "C21") (pin "1") (pinfunction "1_1") (pintype "passive"))
      (node (ref "C22") (pin "1") (pinfunction "1_1") (pintype "passive"))
      (node (ref "C23") (pin "1") (pinfunction "1_1") (pintype "passive"))
      (node (ref "C24") (pin "1") (pinfunction "1_1") (pintype "passive"))
      (node (ref "C25") (pin "1") (pinfunction "1_1") (pintype "passive"))
      (node (ref "C26") (pin "1") (pinfunction "1_1") (pintype "passive"))
      (node (ref "C27") (pin "1") (pinfunction "1_1") (pintype "passive"))
      (node (ref "C28") (pin "1") (pinfunction "1_1") (pintype "passive"))
      (node (ref "C29") (pin "1") (pinfunction "1_1") (pintype "passive"))
      (node (ref "C3") (pin "1") (pinfunction "1_1") (pintype "passive"))
      (node (ref "C30") (pin "1") (pinfunction "1_1") (pintype "passive"))
      (node (ref "C34") (pin "+") (pinfunction "+_+") (pintype "passive"))
      (node (ref "C35") (pin "+") (pinfunction "+_+") (pintype "passive"))
      (node (ref "C36") (pin "+") (pinfunction "+_+") (pintype "passive"))
      (node (ref "C4") (pin "1") (pinfunction "1_1") (pintype "passive"))
      (node (ref "C5") (pin "1") (pinfunction "1_1") (pintype "passive"))
      (node (ref "C6") (pin "1") (pinfunction "1_1") (pintype "passive"))
      (node (ref "C7") (pin "1") (pinfunction "1_1") (pintype "passive"))
      (node (ref "C8") (pin "1") (pinfunction "1_1") (pintype "passive"))
      (node (ref "C9") (pin "1") (pinfunction "1_1") (pintype "passive"))
      (node (ref "OMNIBUS") (pin "AA2") (pinfunction "1_AA2") (pintype "bidirectional"))
      (node (ref "OMNIBUS") (pin "BA2") (pinfunction "1_BA2") (pintype "bidirectional"))
      (node (ref "OMNIBUS") (pin "CA2") (pinfunction "1_CA2") (pintype "bidirectional"))
      (node (ref "R10") (pin "2") (pinfunction "2_2") (pintype "passive"))
      (node (ref "R12") (pin "2") (pinfunction "2_2") (pintype "passive"))
      (node (ref "R15") (pin "2") (pinfunction "2_2") (pintype "passive"))
      (node (ref "R16") (pin "2") (pinfunction "2_2") (pintype "passive"))
      (node (ref "R19") (pin "2") (pinfunction "2_2") (pintype "passive"))
      (node (ref "R2") (pin "2") (pinfunction "2_2") (pintype "passive"))
      (node (ref "R20") (pin "2") (pinfunction "2_2") (pintype "passive"))
      (node (ref "R23") (pin "2") (pinfunction "2_2") (pintype "passive"))
      (node (ref "R24") (pin "2") (pinfunction "2_2") (pintype "passive"))
      (node (ref "R27") (pin "2") (pinfunction "2_2") (pintype "passive"))
      (node (ref "R28") (pin "2") (pinfunction "2_2") (pintype "passive"))
      (node (ref "R29") (pin "2") (pinfunction "2_2") (pintype "passive"))
      (node (ref "R5") (pin "2") (pinfunction "2_2") (pintype "passive"))
      (node (ref "R6") (pin "2") (pinfunction "2_2") (pintype "passive"))
      (node (ref "R9") (pin "2") (pinfunction "2_2") (pintype "passive"))
    )
    (net (code "158") (name "WRITE") (class "Default")
      (node (ref "F") (pin "F1") (pinfunction "P_F1") (pintype "passive"))
      (node (ref "H") (pin "M2") (pinfunction "P_M2") (pintype "passive"))
    )
    (net (code "159") (name "unconnected-(E2A-Q4-Pad12)") (class "Default")
      (node (ref "E2") (pin "12") (pinfunction "Q4_12") (pintype "output"))
    )
    (net (code "160") (name "unconnected-(E3A-Q4-Pad12)") (class "Default")
      (node (ref "E3") (pin "12") (pinfunction "Q4_12") (pintype "output"))
    )
    (net (code "161") (name "unconnected-(E8A-RCO-Pad15)") (class "Default")
      (node (ref "E8") (pin "15") (pinfunction "RCO_15") (pintype "output"))
    )
    (net (code "162") (name "unconnected-(E9A-I9-Pad9)") (class "Default")
      (node (ref "E9") (pin "9") (pinfunction "I9_9") (pintype "passive"))
    )
    (net (code "163") (name "unconnected-(E10A-2C-Pad15)") (class "Default")
      (node (ref "E10") (pin "15") (pinfunction "2C_15") (pintype "input"))
    )
    (net (code "164") (name "unconnected-(E10A-2G-Pad14)") (class "Default")
      (node (ref "E10") (pin "14") (pinfunction "2G_14") (pintype "input"))
    )
    (net (code "165") (name "unconnected-(E10A-2Y0-Pad9)") (class "Default")
      (node (ref "E10") (pin "9") (pinfunction "2Y0_9") (pintype "output"))
    )
    (net (code "166") (name "unconnected-(E10A-2Y1-Pad10)") (class "Default")
      (node (ref "E10") (pin "10") (pinfunction "2Y1_10") (pintype "output"))
    )
    (net (code "167") (name "unconnected-(E10A-2Y2-Pad11)") (class "Default")
      (node (ref "E10") (pin "11") (pinfunction "2Y2_11") (pintype "output"))
    )
    (net (code "168") (name "unconnected-(E10A-2Y3-Pad12)") (class "Default")
      (node (ref "E10") (pin "12") (pinfunction "2Y3_12") (pintype "output"))
    )
    (net (code "169") (name "unconnected-(E17A-Q4-Pad12)") (class "Default")
      (node (ref "E17") (pin "12") (pinfunction "Q4_12") (pintype "output"))
    )
    (net (code "170") (name "unconnected-(E42E-O-Pad10)") (class "Default")
      (node (ref "E42") (pin "10") (pinfunction "O_10") (pintype "output"))
    )
    (net (code "171") (name "~{6RK3_OK}") (class "Default")
      (node (ref "E49") (pin "4") (pinfunction "I0_4") (pintype "input"))
      (node (ref "H") (pin "S2") (pinfunction "P_S2") (pintype "passive"))
    )
    (net (code "172") (name "~{6RK4}") (class "Default")
      (node (ref "E18") (pin "9") (pinfunction "LD_9") (pintype "input"))
      (node (ref "E21") (pin "9") (pinfunction "LD_9") (pintype "input"))
      (node (ref "E47") (pin "11") (pinfunction "I0_11") (pintype "input"))
      (node (ref "E8") (pin "9") (pinfunction "LD_9") (pintype "input"))
      (node (ref "J") (pin "S2") (pinfunction "P_S2") (pintype "passive"))
    )
    (net (code "173") (name "~{AC7}") (class "Default")
      (node (ref "E30") (pin "4") (pinfunction "I0_4") (pintype "input"))
      (node (ref "H") (pin "B1") (pinfunction "P_B1") (pintype "passive"))
    )
    (net (code "174") (name "~{BDATA2}") (class "Default")
      (node (ref "E31") (pin "2") (pinfunction "I1_2") (pintype "input"))
      (node (ref "E43") (pin "6") (pinfunction "O_6") (pintype "output"))
    )
    (net (code "175") (name "~{BDATA10}") (class "Default")
      (node (ref "E43") (pin "12") (pinfunction "O_12") (pintype "output"))
      (node (ref "E47") (pin "8") (pinfunction "I0_8") (pintype "input"))
      (node (ref "J") (pin "P2") (pinfunction "P_P2") (pintype "passive"))
    )
    (net (code "176") (name "~{BDATA11}") (class "Default")
      (node (ref "E43") (pin "10") (pinfunction "O_10") (pintype "output"))
      (node (ref "J") (pin "H1") (pinfunction "P_H1") (pintype "passive"))
    )
    (net (code "177") (name "~{BK_CYCLE}") (class "Default")
      (node (ref "E26") (pin "1") (pinfunction "O_1") (pintype "open_collector"))
      (node (ref "OMNIBUS") (pin "BL2") (pinfunction "1_BL2") (pintype "bidirectional"))
    )
    (net (code "178") (name "~{BRK_DIR}") (class "Default")
      (node (ref "E1") (pin "12") (pinfunction "I1_12") (pintype "input"))
      (node (ref "E35") (pin "6") (pinfunction "~{Q}_6") (pintype "output"))
      (node (ref "H") (pin "P2") (pinfunction "P_P2") (pintype "passive"))
    )
    (net (code "179") (name "~{BRK_ENABLE}") (class "Default")
      (node (ref "E48") (pin "5") (pinfunction "Q_5") (pintype "output"))
    )
    (net (code "180") (name "~{BRK_IN_PROG}") (class "Default")
      (node (ref "E26") (pin "10") (pinfunction "O_10") (pintype "open_collector"))
      (node (ref "OMNIBUS") (pin "BE2") (pinfunction "1_BE2") (pintype "bidirectional"))
    )
    (net (code "181") (name "~{BRK_IN}") (class "Default")
      (node (ref "E46") (pin "12") (pinfunction "I2_12") (pintype "input"))
      (node (ref "E48") (pin "9") (pinfunction "Q_9") (pintype "output"))
    )
    (net (code "182") (name "~{BTP3}") (class "Default")
      (node (ref "E41") (pin "10") (pinfunction "I1_10") (pintype "input"))
      (node (ref "J") (pin "U1") (pinfunction "P_U1") (pintype "passive"))
    )
    (net (code "183") (name "~{CLR_ALL}") (class "Default")
      (node (ref "E") (pin "H1") (pinfunction "P_H1") (pintype "passive"))
      (node (ref "E17") (pin "1") (pinfunction "R_1") (pintype "input"))
      (node (ref "E18") (pin "1") (pinfunction "CLR_1") (pintype "input"))
      (node (ref "E2") (pin "1") (pinfunction "R_1") (pintype "input"))
      (node (ref "E21") (pin "1") (pinfunction "CLR_1") (pintype "input"))
      (node (ref "E3") (pin "1") (pinfunction "R_1") (pintype "input"))
      (node (ref "E34") (pin "1") (pinfunction "CLR_1") (pintype "input"))
      (node (ref "E35") (pin "1") (pinfunction "CLR_1") (pintype "input"))
      (node (ref "E39") (pin "1") (pinfunction "CLR_1") (pintype "input"))
      (node (ref "E39") (pin "13") (pinfunction "CLR_13") (pintype "input"))
      (node (ref "E45") (pin "1") (pinfunction "CLR_1") (pintype "input"))
      (node (ref "E8") (pin "1") (pinfunction "CLR_1") (pintype "input"))
      (node (ref "J") (pin "U2") (pinfunction "P_U2") (pintype "passive"))
    )
    (net (code "184") (name "~{CLR_CNTRS}") (class "Default")
      (node (ref "E25") (pin "1") (pinfunction "I0_1") (pintype "input"))
      (node (ref "F") (pin "S1") (pinfunction "P_S1") (pintype "passive"))
    )
    (net (code "185") (name "~{CLR_DRIVE_CMD}") (class "Default")
      (node (ref "F") (pin "B2") (pinfunction "P_B2") (pintype "passive"))
      (node (ref "J") (pin "C2") (pinfunction "P_C2") (pintype "passive"))
    )
    (net (code "186") (name "~{CLR_DSK_AD}") (class "Default")
      (node (ref "E14") (pin "16") (pinfunction "CLR_16") (pintype "input"))
      (node (ref "E23") (pin "1") (pinfunction "CLR_1") (pintype "input"))
      (node (ref "E24") (pin "1") (pinfunction "I0_1") (pintype "input"))
      (node (ref "E29") (pin "11") (pinfunction "O_11") (pintype "output"))
      (node (ref "E4") (pin "16") (pinfunction "CLR_16") (pintype "input"))
    )
    (net (code "187") (name "~{CLR_SECTOR_AD}") (class "Default")
      (node (ref "E") (pin "F1") (pinfunction "P_F1") (pintype "passive"))
      (node (ref "E19") (pin "3") (pinfunction "O_3") (pintype "output"))
    )
    (net (code "188") (name "~{CPMA_DIS}") (class "Default")
      (node (ref "E38") (pin "10") (pinfunction "O_10") (pintype "open_collector"))
      (node (ref "OMNIBUS") (pin "CU1") (pinfunction "1_CU1") (pintype "bidirectional"))
    )
    (net (code "189") (name "~{CRC_MAIN_DATA}") (class "Default")
      (node (ref "E31") (pin "12") (pinfunction "I0_12") (pintype "input"))
      (node (ref "E40") (pin "3") (pinfunction "O_3") (pintype "output"))
    )
    (net (code "190") (name "~{CRC_MAIN_SHFT}") (class "Default")
      (node (ref "E31") (pin "10") (pinfunction "I1_10") (pintype "input"))
      (node (ref "E40") (pin "6") (pinfunction "O_6") (pintype "output"))
    )
    (net (code "191") (name "~{DATA0}") (class "Default")
      (node (ref "E13") (pin "10") (pinfunction "I1_10") (pintype "input"))
      (node (ref "OMNIBUS") (pin "AR1") (pinfunction "1_AR1") (pintype "bidirectional"))
      (node (ref "W3") (pin "1") (pinfunction "1_1") (pintype "passive"))
      (node (ref "W4") (pin "2") (pinfunction "2_2") (pintype "passive"))
    )
    (net (code "192") (name "~{DATA1}") (class "Default")
      (node (ref "E13") (pin "12") (pinfunction "I1_12") (pintype "input"))
      (node (ref "OMNIBUS") (pin "AS1") (pinfunction "1_AS1") (pintype "bidirectional"))
      (node (ref "W5") (pin "1") (pinfunction "1_1") (pintype "passive"))
    )
    (net (code "193") (name "~{DATA2}") (class "Default")
      (node (ref "E13") (pin "6") (pinfunction "I0_6") (pintype "input"))
      (node (ref "OMNIBUS") (pin "AU1") (pinfunction "1_AU1") (pintype "bidirectional"))
    )
    (net (code "194") (name "~{DATA3}") (class "Default")
      (node (ref "E13") (pin "5") (pinfunction "I1_5") (pintype "input"))
      (node (ref "OMNIBUS") (pin "AV1") (pinfunction "1_AV1") (pintype "bidirectional"))
    )
    (net (code "195") (name "~{DATA4}") (class "Default")
      (node (ref "E22") (pin "12") (pinfunction "I1_12") (pintype "input"))
      (node (ref "OMNIBUS") (pin "BR1") (pinfunction "1_BR1") (pintype "bidirectional"))
    )
    (net (code "196") (name "~{DATA5}") (class "Default")
      (node (ref "E22") (pin "9") (pinfunction "I0_9") (pintype "input"))
      (node (ref "OMNIBUS") (pin "BS1") (pinfunction "1_BS1") (pintype "bidirectional"))
    )
    (net (code "197") (name "~{DATA6}") (class "Default")
      (node (ref "E22") (pin "4") (pinfunction "I0_4") (pintype "input"))
      (node (ref "OMNIBUS") (pin "BU1") (pinfunction "1_BU1") (pintype "bidirectional"))
    )
    (net (code "198") (name "~{DATA7}") (class "Default")
      (node (ref "E22") (pin "7") (pinfunction "I1_7") (pintype "input"))
      (node (ref "OMNIBUS") (pin "BV1") (pinfunction "1_BV1") (pintype "bidirectional"))
    )
    (net (code "199") (name "~{DATA_ENABLE}") (class "Default")
      (node (ref "E36") (pin "1") (pinfunction "I0_1") (pintype "input"))
      (node (ref "E39") (pin "8") (pinfunction "~{Q}_8") (pintype "output"))
    )
    (net (code "200") (name "~{DATA_ENAB}") (class "Default")
      (node (ref "E") (pin "V1") (pinfunction "P_V1") (pintype "passive"))
      (node (ref "E13") (pin "11") (pinfunction "I0_11") (pintype "input"))
      (node (ref "E13") (pin "4") (pinfunction "I0_4") (pintype "input"))
      (node (ref "E13") (pin "7") (pinfunction "I1_7") (pintype "input"))
      (node (ref "E13") (pin "9") (pinfunction "I0_9") (pintype "input"))
      (node (ref "E22") (pin "10") (pinfunction "I1_10") (pintype "input"))
      (node (ref "E22") (pin "11") (pinfunction "I0_11") (pintype "input"))
      (node (ref "E22") (pin "5") (pinfunction "I1_5") (pintype "input"))
      (node (ref "E22") (pin "6") (pinfunction "I0_6") (pintype "input"))
      (node (ref "E38") (pin "1") (pinfunction "O_1") (pintype "open_collector"))
      (node (ref "R29") (pin "1") (pinfunction "1_1") (pintype "passive"))
    )
    (net (code "201") (name "~{DATA_IN}") (class "Default")
      (node (ref "E31") (pin "13") (pinfunction "I1_13") (pintype "input"))
      (node (ref "E49") (pin "13") (pinfunction "I1_13") (pintype "input"))
      (node (ref "F") (pin "R1") (pinfunction "P_R1") (pintype "passive"))
    )
    (net (code "202") (name "~{DATA_STATE}") (class "Default")
      (node (ref "E29") (pin "4") (pinfunction "I0_4") (pintype "input"))
      (node (ref "E42") (pin "9") (pinfunction "I_9") (pintype "input"))
      (node (ref "E49") (pin "5") (pinfunction "I1_5") (pintype "input"))
      (node (ref "F") (pin "P1") (pinfunction "P_P1") (pintype "passive"))
      (node (ref "J") (pin "M2") (pinfunction "P_M2") (pintype "passive"))
    )
    (net (code "203") (name "~{DB_CONT1}") (class "Default")
      (node (ref "E46") (pin "13") (pinfunction "I3_13") (pintype "input"))
      (node (ref "H") (pin "V1") (pinfunction "P_V1") (pintype "passive"))
    )
    (net (code "204") (name "~{DRIVE0}") (class "Default")
      (node (ref "E10") (pin "7") (pinfunction "1Y0_7") (pintype "output"))
      (node (ref "E11") (pin "6") (pinfunction "I0_6") (pintype "input"))
      (node (ref "E11") (pin "7") (pinfunction "I1_7") (pintype "input"))
    )
    (net (code "205") (name "~{DRIVE1}") (class "Default")
      (node (ref "E10") (pin "6") (pinfunction "1Y1_6") (pintype "output"))
      (node (ref "E11") (pin "1") (pinfunction "I0_1") (pintype "input"))
      (node (ref "E11") (pin "2") (pinfunction "I1_2") (pintype "input"))
    )
    (net (code "206") (name "~{DRIVE2}") (class "Default")
      (node (ref "E10") (pin "5") (pinfunction "1Y2_5") (pintype "output"))
      (node (ref "E12") (pin "6") (pinfunction "I0_6") (pintype "input"))
      (node (ref "E12") (pin "7") (pinfunction "I1_7") (pintype "input"))
    )
    (net (code "207") (name "~{DRIVE3}") (class "Default")
      (node (ref "E10") (pin "4") (pinfunction "1Y3_4") (pintype "output"))
      (node (ref "E12") (pin "1") (pinfunction "I0_1") (pintype "input"))
      (node (ref "E12") (pin "2") (pinfunction "I1_2") (pintype "input"))
    )
    (net (code "208") (name "~{DSK_CAPACITY_EX}") (class "Default")
      (node (ref "F") (pin "C1") (pinfunction "P_C1") (pintype "passive"))
      (node (ref "J") (pin "K1") (pinfunction "P_K1") (pintype "passive"))
    )
    (net (code "209") (name "~{DSK_CYL_AD1}") (class "Default")
      (node (ref "E") (pin "S1") (pinfunction "P_S1") (pintype "passive"))
      (node (ref "E5") (pin "3") (pinfunction "O_3") (pintype "open_collector"))
      (node (ref "R7") (pin "2") (pinfunction "2_2") (pintype "passive"))
      (node (ref "R9") (pin "1") (pinfunction "1_1") (pintype "passive"))
    )
    (net (code "210") (name "~{DSK_CYL_AD2}") (class "Default")
      (node (ref "E") (pin "K2") (pinfunction "P_K2") (pintype "passive"))
      (node (ref "E6") (pin "5") (pinfunction "O_5") (pintype "open_collector"))
      (node (ref "R3") (pin "2") (pinfunction "2_2") (pintype "passive"))
      (node (ref "R5") (pin "1") (pinfunction "1_1") (pintype "passive"))
    )
    (net (code "211") (name "~{DSK_CYL_AD4}") (class "Default")
      (node (ref "E") (pin "H2") (pinfunction "P_H2") (pintype "passive"))
      (node (ref "E6") (pin "3") (pinfunction "O_3") (pintype "open_collector"))
      (node (ref "R1") (pin "2") (pinfunction "2_2") (pintype "passive"))
      (node (ref "R2") (pin "1") (pinfunction "1_1") (pintype "passive"))
    )
    (net (code "212") (name "~{DSK_CYL_AD8}") (class "Default")
      (node (ref "E") (pin "T1") (pinfunction "P_T1") (pintype "passive"))
      (node (ref "E5") (pin "5") (pinfunction "O_5") (pintype "open_collector"))
      (node (ref "R11") (pin "2") (pinfunction "2_2") (pintype "passive"))
      (node (ref "R12") (pin "1") (pinfunction "1_1") (pintype "passive"))
    )
    (net (code "213") (name "~{DSK_CYL_AD16}") (class "Default")
      (node (ref "E") (pin "C2") (pinfunction "P_C2") (pintype "passive"))
      (node (ref "E15") (pin "3") (pinfunction "O_3") (pintype "open_collector"))
      (node (ref "R18") (pin "2") (pinfunction "2_2") (pintype "passive"))
      (node (ref "R20") (pin "1") (pinfunction "1_1") (pintype "passive"))
    )
    (net (code "214") (name "~{DSK_CYL_AD32}") (class "Default")
      (node (ref "E") (pin "J2") (pinfunction "P_J2") (pintype "passive"))
      (node (ref "E15") (pin "5") (pinfunction "O_5") (pintype "open_collector"))
      (node (ref "R10") (pin "1") (pinfunction "1_1") (pintype "passive"))
      (node (ref "R8") (pin "2") (pinfunction "2_2") (pintype "passive"))
    )
    (net (code "215") (name "~{DSK_CYL_AD64}") (class "Default")
      (node (ref "E") (pin "B2") (pinfunction "P_B2") (pintype "passive"))
      (node (ref "E16") (pin "5") (pinfunction "O_5") (pintype "open_collector"))
      (node (ref "R22") (pin "2") (pinfunction "2_2") (pintype "passive"))
      (node (ref "R24") (pin "1") (pinfunction "1_1") (pintype "passive"))
    )
    (net (code "216") (name "~{DSK_CYL_AD128}") (class "Default")
      (node (ref "E") (pin "E2") (pinfunction "P_E2") (pintype "passive"))
      (node (ref "E16") (pin "3") (pinfunction "O_3") (pintype "open_collector"))
      (node (ref "R14") (pin "2") (pinfunction "2_2") (pintype "passive"))
      (node (ref "R16") (pin "1") (pinfunction "1_1") (pintype "passive"))
    )
    (net (code "217") (name "~{DSK_DRIVE0}") (class "Default")
      (node (ref "E") (pin "D2") (pinfunction "P_D2") (pintype "passive"))
      (node (ref "E11") (pin "5") (pinfunction "O_5") (pintype "open_collector"))
      (node (ref "R17") (pin "2") (pinfunction "2_2") (pintype "passive"))
      (node (ref "R19") (pin "1") (pinfunction "1_1") (pintype "passive"))
    )
    (net (code "218") (name "~{DSK_DRIVE1}") (class "Default")
      (node (ref "E") (pin "R1") (pinfunction "P_R1") (pintype "passive"))
      (node (ref "E11") (pin "3") (pinfunction "O_3") (pintype "open_collector"))
      (node (ref "R13") (pin "2") (pinfunction "2_2") (pintype "passive"))
      (node (ref "R15") (pin "1") (pinfunction "1_1") (pintype "passive"))
    )
    (net (code "219") (name "~{DSK_DRIVE2}") (class "Default")
      (node (ref "E") (pin "P1") (pinfunction "P_P1") (pintype "passive"))
      (node (ref "E12") (pin "5") (pinfunction "O_5") (pintype "open_collector"))
      (node (ref "R21") (pin "2") (pinfunction "2_2") (pintype "passive"))
      (node (ref "R23") (pin "1") (pinfunction "1_1") (pintype "passive"))
    )
    (net (code "220") (name "~{DSK_DRIVE3}") (class "Default")
      (node (ref "E") (pin "N1") (pinfunction "P_N1") (pintype "passive"))
      (node (ref "E12") (pin "3") (pinfunction "O_3") (pintype "open_collector"))
      (node (ref "R25") (pin "2") (pinfunction "2_2") (pintype "passive"))
      (node (ref "R27") (pin "1") (pinfunction "1_1") (pintype "passive"))
    )
    (net (code "221") (name "~{DSK_FILE_RDY}") (class "Default")
      (node (ref "F") (pin "B1") (pinfunction "P_B1") (pintype "passive"))
      (node (ref "H") (pin "E1") (pinfunction "P_E1") (pintype "passive"))
    )
    (net (code "222") (name "~{DSK_RDY_S-R-W}") (class "Default")
      (node (ref "E") (pin "L2") (pinfunction "P_L2") (pintype "passive"))
      (node (ref "E32") (pin "10") (pinfunction "I1_10") (pintype "input"))
      (node (ref "R4") (pin "2") (pinfunction "2_2") (pintype "passive"))
      (node (ref "R6") (pin "1") (pinfunction "1_1") (pintype "passive"))
    )
    (net (code "223") (name "~{DSK_SEEK_FAIL}") (class "Default")
      (node (ref "E") (pin "A2") (pinfunction "P_A2") (pintype "passive"))
      (node (ref "E42") (pin "3") (pinfunction "I_3") (pintype "input"))
      (node (ref "R26") (pin "2") (pinfunction "2_2") (pintype "passive"))
      (node (ref "R28") (pin "1") (pinfunction "1_1") (pintype "passive"))
    )
    (net (code "224") (name "~{DSK_WRT_STATUS}") (class "Default")
      (node (ref "F") (pin "D2") (pinfunction "P_D2") (pintype "passive"))
      (node (ref "J") (pin "D2") (pinfunction "P_D2") (pintype "passive"))
    )
    (net (code "225") (name "~{EMA0}") (class "Default")
      (node (ref "E1") (pin "10") (pinfunction "O_10") (pintype "open_collector"))
      (node (ref "OMNIBUS") (pin "AD2") (pinfunction "1_AD2") (pintype "bidirectional"))
    )
    (net (code "226") (name "~{EMA1}") (class "Default")
      (node (ref "E1") (pin "4") (pinfunction "O_4") (pintype "open_collector"))
      (node (ref "OMNIBUS") (pin "AE2") (pinfunction "1_AE2") (pintype "bidirectional"))
    )
    (net (code "227") (name "~{EMA2}") (class "Default")
      (node (ref "E1") (pin "1") (pinfunction "O_1") (pintype "open_collector"))
      (node (ref "OMNIBUS") (pin "AH2") (pinfunction "1_AH2") (pintype "bidirectional"))
    )
    (net (code "228") (name "~{END_STATE}") (class "Default")
      (node (ref "F") (pin "D1") (pinfunction "P_D1") (pintype "passive"))
      (node (ref "J") (pin "J2") (pinfunction "P_J2") (pintype "passive"))
    )
    (net (code "229") (name "~{ERROR_CLR}") (class "Default")
      (node (ref "F") (pin "E2") (pinfunction "P_E2") (pintype "passive"))
      (node (ref "J") (pin "D1") (pinfunction "P_D1") (pintype "passive"))
    )
    (net (code "230") (name "~{HI_MAIN_DATA}") (class "Default")
      (node (ref "E49") (pin "12") (pinfunction "I0_12") (pintype "input"))
      (node (ref "E49") (pin "3") (pinfunction "O_3") (pintype "output"))
    )
    (net (code "231") (name "~{HI_MAIN_SHFT}") (class "Default")
      (node (ref "E37") (pin "12") (pinfunction "O_12") (pintype "output"))
      (node (ref "E49") (pin "10") (pinfunction "I1_10") (pintype "input"))
      (node (ref "F") (pin "T2") (pinfunction "P_T2") (pintype "passive"))
    )
    (net (code "232") (name "~{IDLE}") (class "Default")
      (node (ref "E47") (pin "12") (pinfunction "I1_12") (pintype "input"))
      (node (ref "F") (pin "R2") (pinfunction "P_R2") (pintype "passive"))
      (node (ref "J") (pin "N1") (pinfunction "P_N1") (pintype "passive"))
    )
    (net (code "233") (name "~{LAST_BRK}") (class "Default")
      (node (ref "E45") (pin "8") (pinfunction "~{Q}_8") (pintype "output"))
      (node (ref "E46") (pin "9") (pinfunction "I0_9") (pintype "input"))
    )
    (net (code "234") (name "~{LD-SHFT_CMD_REG}") (class "Default")
      (node (ref "E17") (pin "6") (pinfunction "C_6") (pintype "input"))
      (node (ref "E2") (pin "6") (pinfunction "C_6") (pintype "input"))
      (node (ref "E3") (pin "6") (pinfunction "C_6") (pintype "input"))
      (node (ref "E47") (pin "4") (pinfunction "O_4") (pintype "output"))
    )
    (net (code "235") (name "~{LO_MAIN_SHFT}") (class "Default")
      (node (ref "E31") (pin "6") (pinfunction "O_6") (pintype "output"))
      (node (ref "F") (pin "L1") (pinfunction "P_L1") (pintype "passive"))
      (node (ref "H") (pin "P1") (pinfunction "P_P1") (pintype "passive"))
    )
    (net (code "236") (name "~{MA0}") (class "Default")
      (node (ref "E7") (pin "13") (pinfunction "O_13") (pintype "open_collector"))
      (node (ref "OMNIBUS") (pin "AD1") (pinfunction "1_AD1") (pintype "bidirectional"))
    )
    (net (code "237") (name "~{MA1}") (class "Default")
      (node (ref "E7") (pin "10") (pinfunction "O_10") (pintype "open_collector"))
      (node (ref "OMNIBUS") (pin "AE1") (pinfunction "1_AE1") (pintype "bidirectional"))
    )
    (net (code "238") (name "~{MA2}") (class "Default")
      (node (ref "E7") (pin "4") (pinfunction "O_4") (pintype "open_collector"))
      (node (ref "OMNIBUS") (pin "AH1") (pinfunction "1_AH1") (pintype "bidirectional"))
    )
    (net (code "239") (name "~{MA3}") (class "Default")
      (node (ref "E7") (pin "1") (pinfunction "O_1") (pintype "open_collector"))
      (node (ref "OMNIBUS") (pin "AJ1") (pinfunction "1_AJ1") (pintype "bidirectional"))
    )
    (net (code "240") (name "~{MA4}") (class "Default")
      (node (ref "E20") (pin "10") (pinfunction "O_10") (pintype "open_collector"))
      (node (ref "OMNIBUS") (pin "BD1") (pinfunction "1_BD1") (pintype "bidirectional"))
    )
    (net (code "241") (name "~{MA5}") (class "Default")
      (node (ref "E20") (pin "13") (pinfunction "O_13") (pintype "open_collector"))
      (node (ref "OMNIBUS") (pin "BE1") (pinfunction "1_BE1") (pintype "bidirectional"))
    )
    (net (code "242") (name "~{MA6}") (class "Default")
      (node (ref "E20") (pin "4") (pinfunction "O_4") (pintype "open_collector"))
      (node (ref "OMNIBUS") (pin "BH1") (pinfunction "1_BH1") (pintype "bidirectional"))
    )
    (net (code "243") (name "~{MA7}") (class "Default")
      (node (ref "E20") (pin "1") (pinfunction "O_1") (pintype "open_collector"))
      (node (ref "OMNIBUS") (pin "BJ1") (pinfunction "1_BJ1") (pintype "bidirectional"))
    )
    (net (code "244") (name "~{MA8}") (class "Default")
      (node (ref "E44") (pin "10") (pinfunction "O_10") (pintype "open_collector"))
      (node (ref "OMNIBUS") (pin "DD1") (pinfunction "1_DD1") (pintype "bidirectional"))
    )
    (net (code "245") (name "~{MA9}") (class "Default")
      (node (ref "E44") (pin "4") (pinfunction "O_4") (pintype "open_collector"))
      (node (ref "OMNIBUS") (pin "DE1") (pinfunction "1_DE1") (pintype "bidirectional"))
    )
    (net (code "246") (name "~{MA10}") (class "Default")
      (node (ref "E44") (pin "1") (pinfunction "O_1") (pintype "open_collector"))
      (node (ref "OMNIBUS") (pin "DH1") (pinfunction "1_DH1") (pintype "bidirectional"))
    )
    (net (code "247") (name "~{MA11}") (class "Default")
      (node (ref "E44") (pin "13") (pinfunction "O_13") (pintype "open_collector"))
      (node (ref "OMNIBUS") (pin "DJ1") (pinfunction "1_DJ1") (pintype "bidirectional"))
    )
    (net (code "248") (name "~{MAIN}") (class "Default")
      (node (ref "E39") (pin "4") (pinfunction "PRE_4") (pintype "input"))
      (node (ref "E39") (pin "6") (pinfunction "~{Q}_6") (pintype "output"))
      (node (ref "E47") (pin "9") (pinfunction "I1_9") (pintype "input"))
      (node (ref "F") (pin "P2") (pinfunction "P_P2") (pintype "passive"))
      (node (ref "J") (pin "E1") (pinfunction "P_E1") (pintype "passive"))
    )
    (net (code "249") (name "~{MAK}") (class "Default")
      (node (ref "E45") (pin "6") (pinfunction "~{Q}_6") (pintype "output"))
      (node (ref "H") (pin "J1") (pinfunction "P_J1") (pintype "passive"))
    )
    (net (code "250") (name "~{MALC}") (class "Default")
      (node (ref "E34") (pin "6") (pinfunction "~{Q}_6") (pintype "output"))
    )
    (net (code "251") (name "~{MAMS_LOAD_CONT}") (class "Default")
      (node (ref "E26") (pin "13") (pinfunction "O_13") (pintype "open_collector"))
      (node (ref "OMNIBUS") (pin "BH2") (pinfunction "1_BH2") (pintype "bidirectional"))
    )
    (net (code "252") (name "~{MD_DIR}") (class "Default")
      (node (ref "E1") (pin "13") (pinfunction "O_13") (pintype "open_collector"))
      (node (ref "OMNIBUS") (pin "AK2") (pinfunction "1_AK2") (pintype "bidirectional"))
    )
    (net (code "253") (name "~{MSIR_DIS}") (class "Default")
      (node (ref "E26") (pin "4") (pinfunction "O_4") (pintype "open_collector"))
      (node (ref "OMNIBUS") (pin "CV1") (pinfunction "1_CV1") (pintype "bidirectional"))
    )
    (net (code "254") (name "~{NBR}") (class "Default")
      (node (ref "E35") (pin "8") (pinfunction "~{Q}_8") (pintype "output"))
      (node (ref "E36") (pin "2") (pinfunction "I1_2") (pintype "input"))
    )
    (net (code "255") (name "~{NOT_EQUAL}") (class "Default")
      (node (ref "E34") (pin "10") (pinfunction "PRE_10") (pintype "input"))
      (node (ref "E34") (pin "8") (pinfunction "~{Q}_8") (pintype "output"))
      (node (ref "J") (pin "F2") (pinfunction "P_F2") (pintype "passive"))
    )
    (net (code "256") (name "~{RDY_S{slash}R{slash}W}") (class "Default")
      (node (ref "E43") (pin "8") (pinfunction "O_8") (pintype "output"))
      (node (ref "H") (pin "U1") (pinfunction "P_U1") (pintype "passive"))
    )
    (net (code "257") (name "~{RD_BRK}") (class "Default")
      (node (ref "E36") (pin "5") (pinfunction "I1_5") (pintype "input"))
      (node (ref "E37") (pin "6") (pinfunction "O_6") (pintype "output"))
      (node (ref "H") (pin "L2") (pinfunction "P_L2") (pintype "passive"))
    )
    (net (code "258") (name "~{RD_SHFT_DB}") (class "Default")
      (node (ref "E49") (pin "9") (pinfunction "I0_9") (pintype "input"))
      (node (ref "F") (pin "S2") (pinfunction "P_S2") (pintype "passive"))
    )
    (net (code "259") (name "~{SECTOR_SEEK}") (class "Default")
      (node (ref "F") (pin "F2") (pinfunction "P_F2") (pintype "passive"))
      (node (ref "J") (pin "F1") (pinfunction "P_F1") (pintype "passive"))
    )
    (net (code "260") (name "~{SET_IDLE_PL}") (class "Default")
      (node (ref "F") (pin "K1") (pinfunction "P_K1") (pintype "passive"))
      (node (ref "J") (pin "J1") (pinfunction "P_J1") (pintype "passive"))
    )
    (net (code "261") (name "~{SET_MAIN_BRK}") (class "Default")
      (node (ref "E36") (pin "11") (pinfunction "O_11") (pintype "output"))
      (node (ref "E42") (pin "13") (pinfunction "I_13") (pintype "input"))
      (node (ref "E48") (pin "1") (pinfunction "CLR_1") (pintype "input"))
    )
    (net (code "262") (name "~{SHFT_WRT_BUFF}") (class "Default")
      (node (ref "F") (pin "J2") (pinfunction "P_J2") (pintype "passive"))
      (node (ref "H") (pin "R2") (pinfunction "P_R2") (pintype "passive"))
    )
    (net (code "263") (name "~{SHIFT_CRC}") (class "Default")
      (node (ref "E31") (pin "9") (pinfunction "I0_9") (pintype "input"))
      (node (ref "F") (pin "N1") (pinfunction "P_N1") (pintype "passive"))
    )
    (net (code "264") (name "~{START_CLR}") (class "Default")
      (node (ref "E25") (pin "2") (pinfunction "I1_2") (pintype "input"))
      (node (ref "E28") (pin "10") (pinfunction "O_10") (pintype "output"))
      (node (ref "E41") (pin "13") (pinfunction "I1_13") (pintype "input"))
      (node (ref "E45") (pin "13") (pinfunction "CLR_13") (pintype "input"))
      (node (ref "E48") (pin "10") (pinfunction "PRE_10") (pintype "input"))
    )
    (net (code "265") (name "~{WRT_BRK}") (class "Default")
      (node (ref "E36") (pin "4") (pinfunction "I0_4") (pintype "input"))
      (node (ref "E46") (pin "8") (pinfunction "O_8") (pintype "output"))
      (node (ref "H") (pin "H1") (pinfunction "P_H1") (pintype "passive"))
    )
    (net (code "266") (name "~{WRT_CMD}") (class "Default")
      (node (ref "E36") (pin "10") (pinfunction "I1_10") (pintype "input"))
      (node (ref "F") (pin "V2") (pinfunction "P_V2") (pintype "passive"))
      (node (ref "J") (pin "E2") (pinfunction "P_E2") (pintype "passive"))
    )
    (net (code "267") (name "~{WT_BUFF_DATA}") (class "Default")
      (node (ref "E37") (pin "8") (pinfunction "O_8") (pintype "output"))
      (node (ref "H") (pin "D2") (pinfunction "P_D2") (pintype "passive"))
    )
  )
)
